# Esquema.net
KiCad netlist of a schematic drawn in Altium Designer
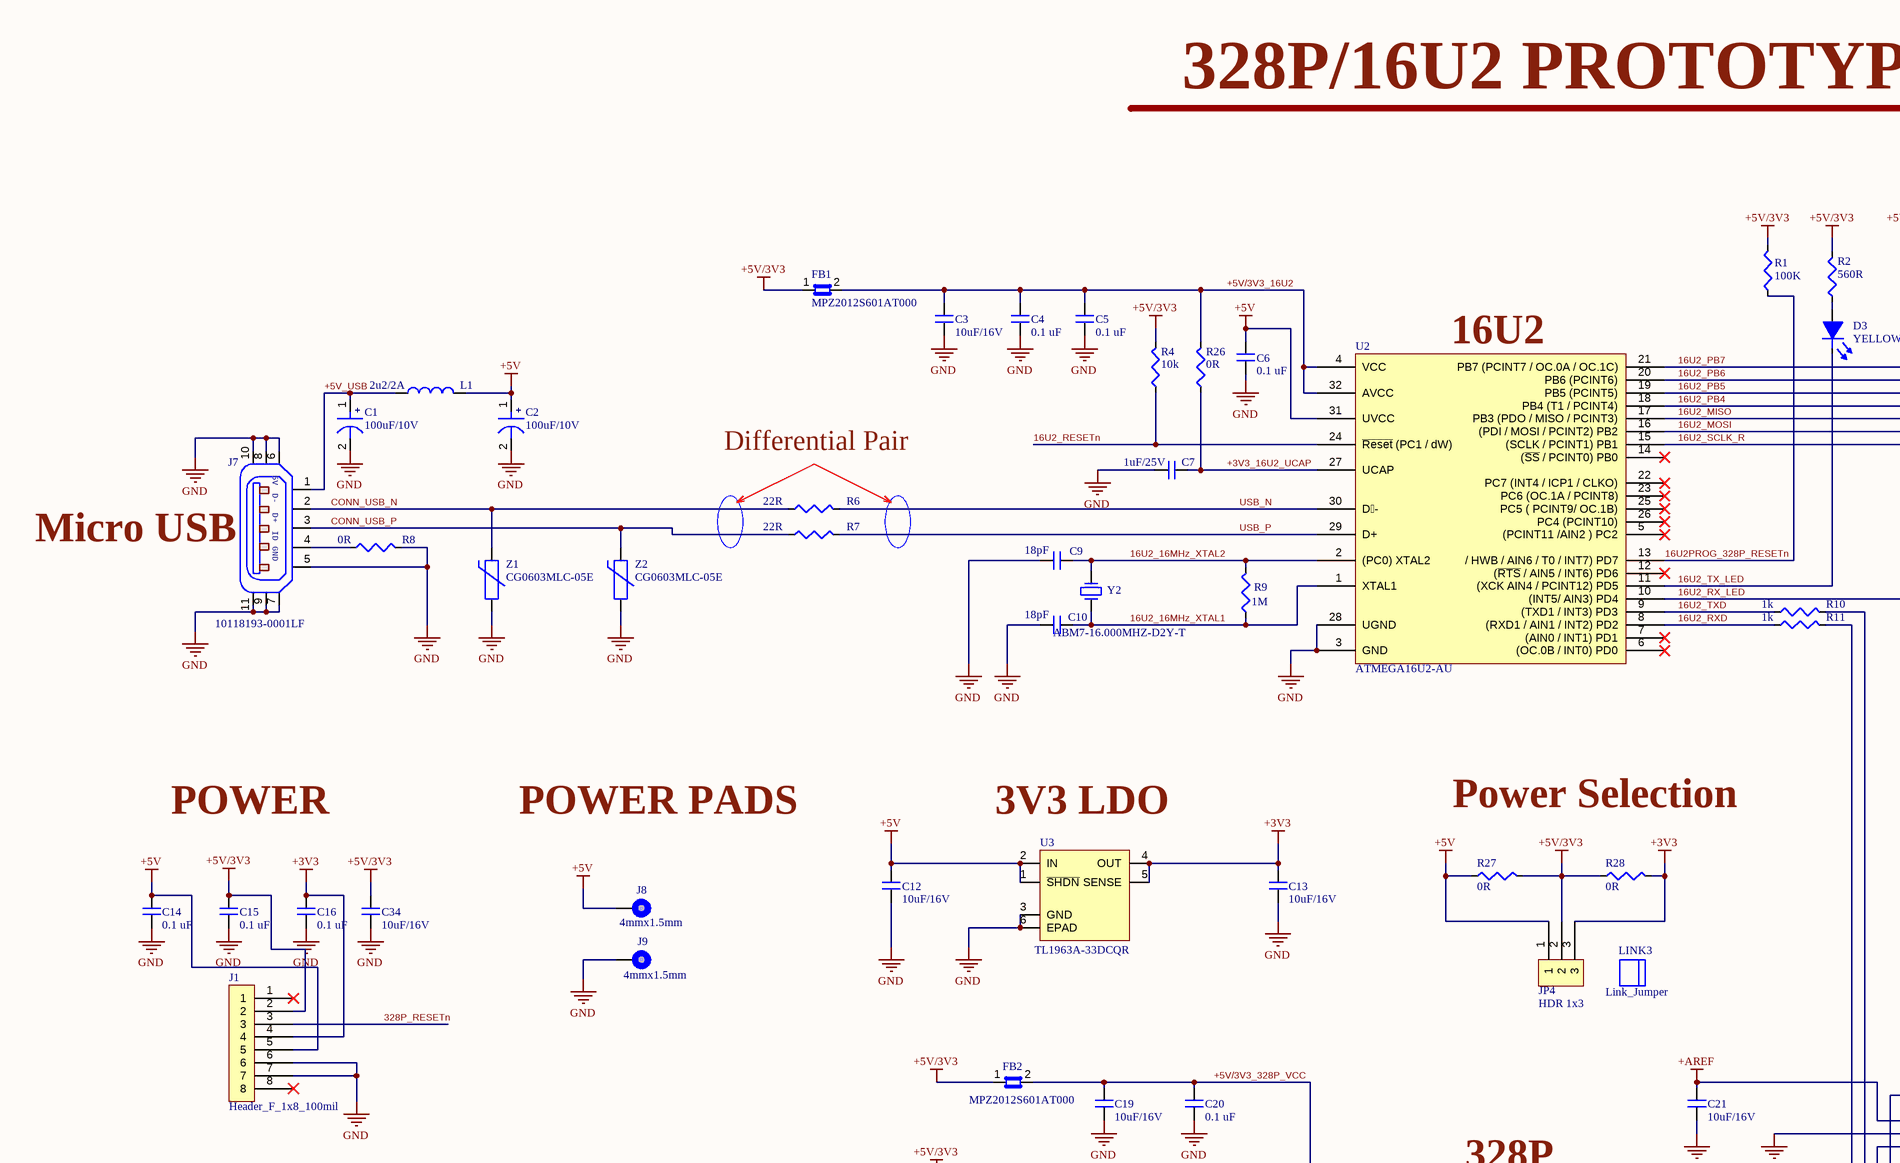
[diagram p0: Esquema.SchDoc, top left]
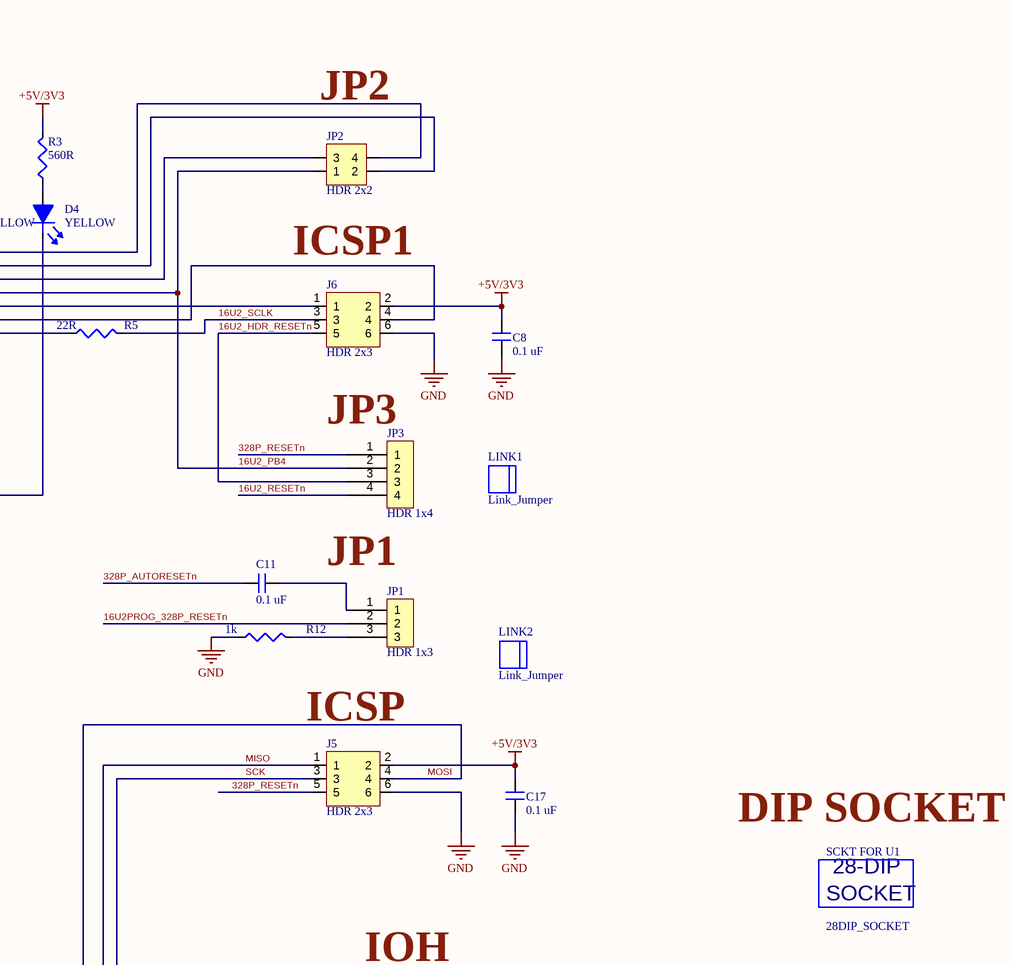
[diagram p1: Esquema.SchDoc, top right]
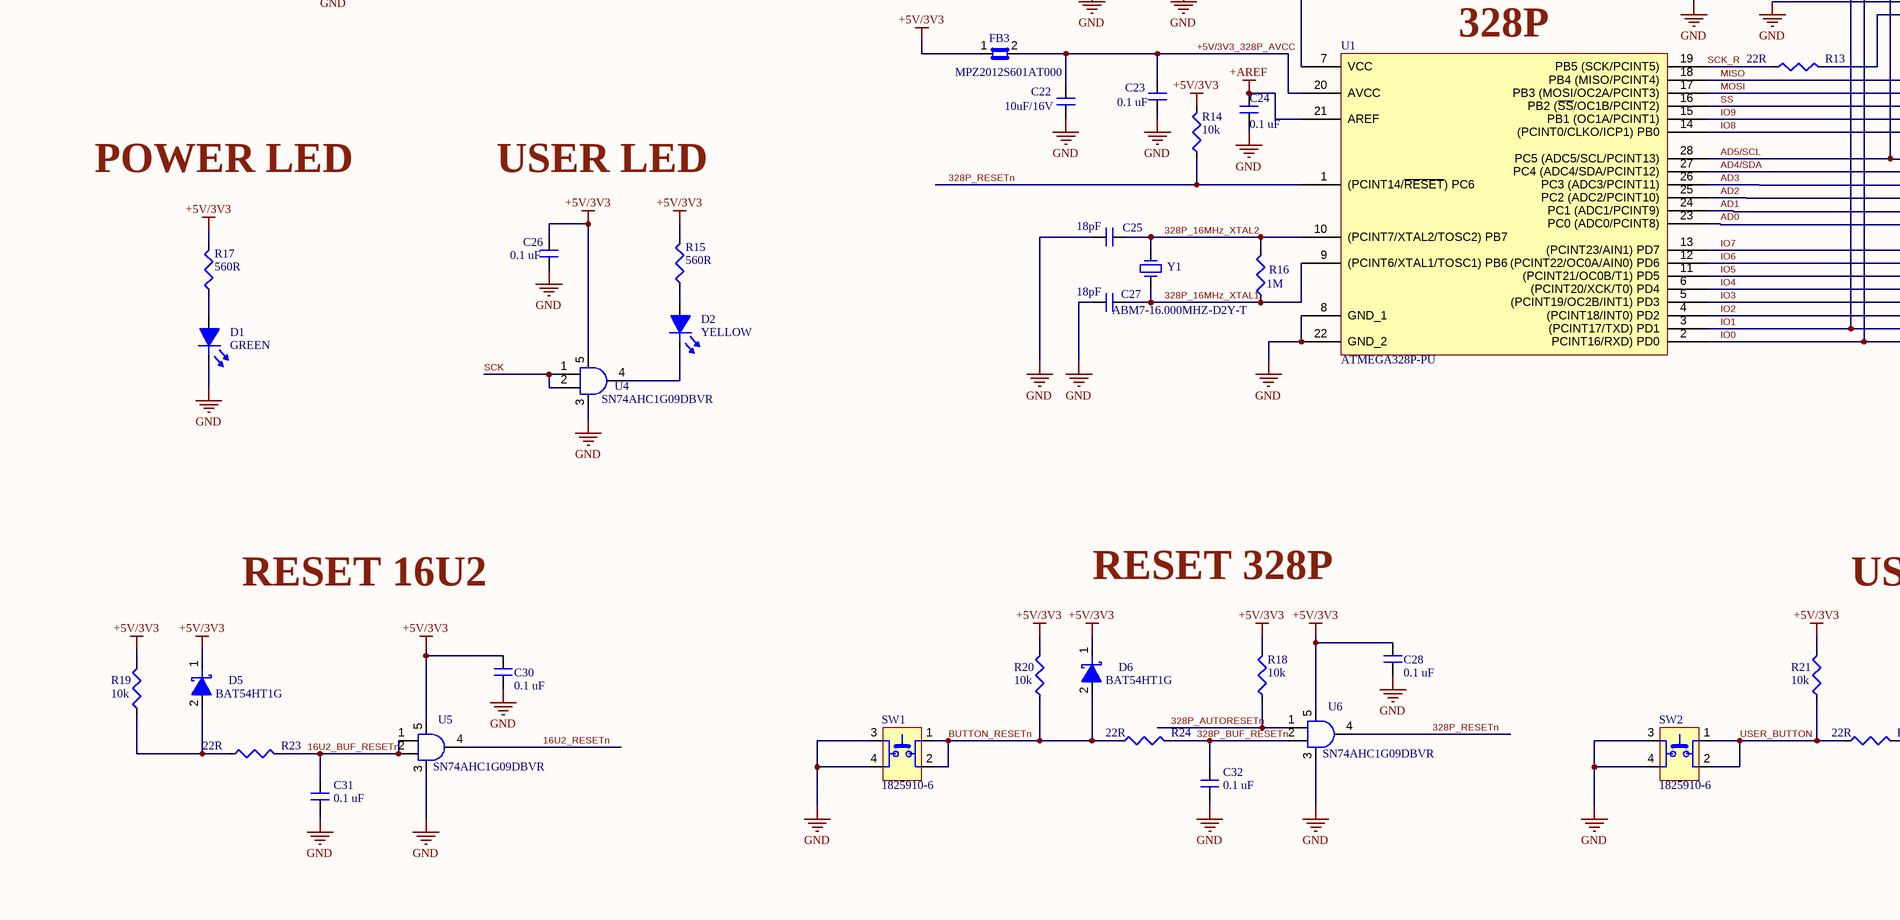
[diagram p2: Esquema.SchDoc, bottom left]
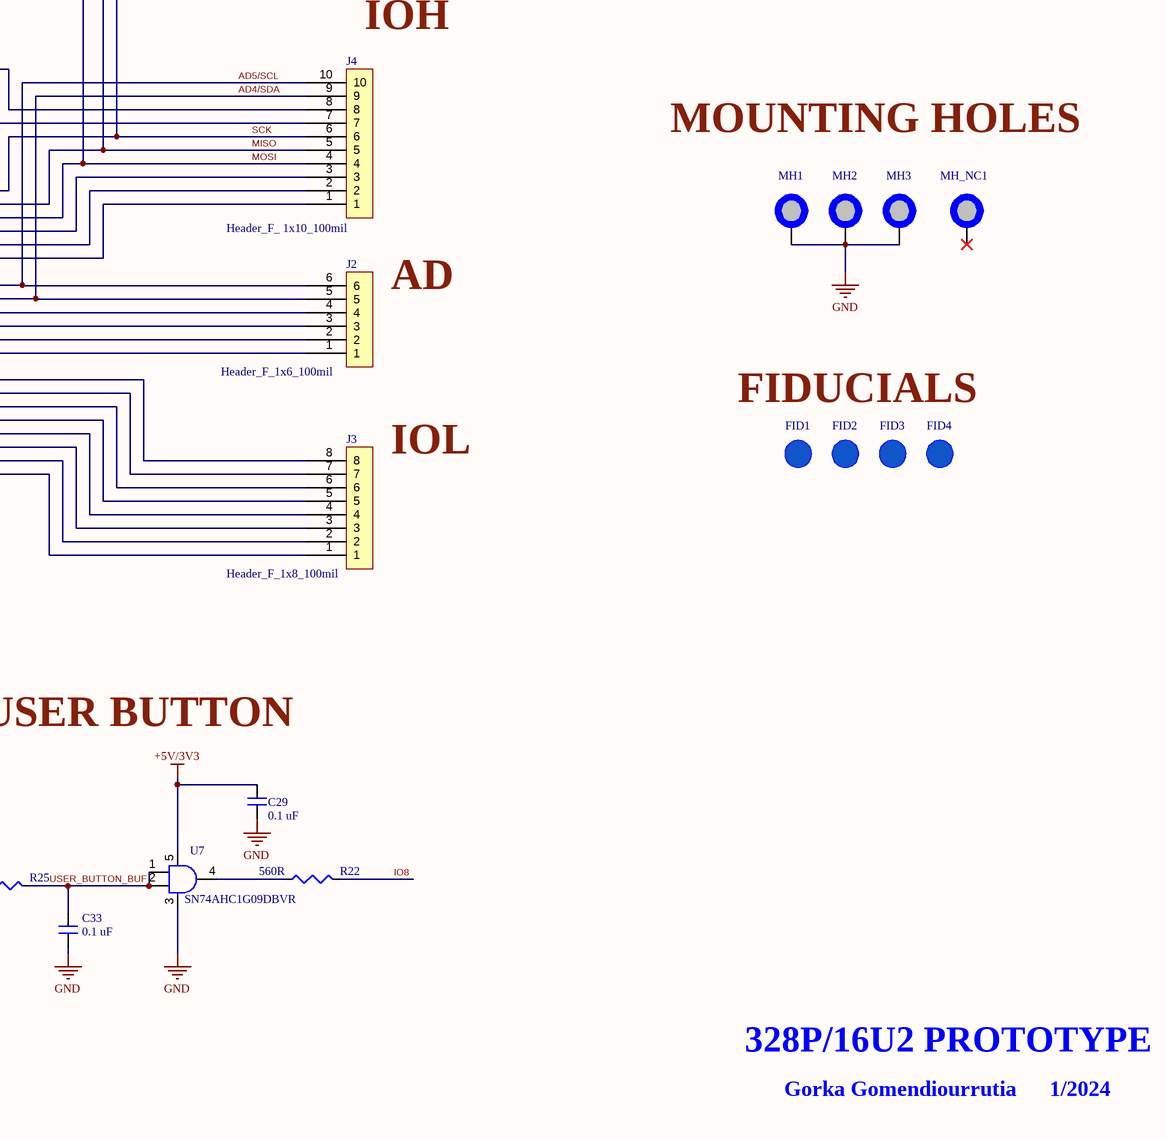
[diagram p3: Esquema.SchDoc, bottom right]

(export (version "E")
  (design (tool "Eeschema 10.0.6"))
  (components
    (comp (ref "C1")
      (value "100uF/10V")
      (footprint "CAP_ALU_C_SIZE")
      (description "Aluminum Electrolytic Capacitor, 100 uF, 10 V, ± 20%, 1000 hours @ 85°C, Radial Can - SMD")
      (fields
        (field (name "MANUFACTURER") "Panasonic")
        (field (name "MANUFACTURER PART NUMBER") "EEE-1AA101WR")
      )
      (libsource (lib "Librerias esquema") (part "EEE-1AA101WR"))
    )
    (comp (ref "C2")
      (value "100uF/10V")
      (footprint "CAP_ALU_C_SIZE")
      (description "Aluminum Electrolytic Capacitor, 100 uF, 10 V, ± 20%, 1000 hours @ 85°C, Radial Can - SMD")
      (fields
        (field (name "MANUFACTURER") "Panasonic")
        (field (name "MANUFACTURER PART NUMBER") "EEE-1AA101WR")
      )
      (libsource (lib "Librerias esquema") (part "EEE-1AA101WR"))
    )
    (comp (ref "C3")
      (value "10uF/16V")
      (footprint "0805")
      (description "C Series 0805 10 uF 16 V ±10 % Tolerance X5R SMT Multilayer Ceramic Capacitor")
      (fields
        (field (name "MANUFACTURER") "TDK")
        (field (name "MANUFACTURER PART NUMBER") "C2012X5R1C106K085AC")
      )
      (libsource (lib "Librerias esquema") (part "C2012X5R1C106K085AC"))
    )
    (comp (ref "C4")
      (value "0.1 uF")
      (footprint "0805")
      (description "Multilayer Ceramic Capacitor, 0.1 uF, 50 V, ± 10%, X7R, 0805 [2012 Metric]")
      (fields
        (field (name "MANUFACTURER") "TDK")
        (field (name "MANUFACTURER PART NUMBER") "C2012X7R1H104K085AA")
      )
      (libsource (lib "Librerias esquema") (part "C2012X7R1H104K085AA"))
    )
    (comp (ref "C5")
      (value "0.1 uF")
      (footprint "0805")
      (description "Multilayer Ceramic Capacitor, 0.1 uF, 50 V, ± 10%, X7R, 0805 [2012 Metric]")
      (fields
        (field (name "MANUFACTURER") "TDK")
        (field (name "MANUFACTURER PART NUMBER") "C2012X7R1H104K085AA")
      )
      (libsource (lib "Librerias esquema") (part "C2012X7R1H104K085AA"))
    )
    (comp (ref "C6")
      (value "0.1 uF")
      (footprint "0805")
      (description "Multilayer Ceramic Capacitor, 0.1 uF, 50 V, ± 10%, X7R, 0805 [2012 Metric]")
      (fields
        (field (name "MANUFACTURER") "TDK")
        (field (name "MANUFACTURER PART NUMBER") "C2012X7R1H104K085AA")
      )
      (libsource (lib "Librerias esquema") (part "C2012X7R1H104K085AA"))
    )
    (comp (ref "C7")
      (value "1uF/25V")
      (footprint "0805")
      (description "C Series 0805 1 uF 25 V ±10 % Tolerance X5R SMT Multilayer Ceramic Capacitor")
      (fields
        (field (name "MANUFACTURER") "TDK")
        (field (name "MANUFACTURER PART NUMBER") "C2012X5R1E105K085AC")
      )
      (libsource (lib "Librerias esquema") (part "C2012X5R1E105K085AC"))
    )
    (comp (ref "C8")
      (value "0.1 uF")
      (footprint "0805")
      (description "Multilayer Ceramic Capacitor, 0.1 uF, 50 V, ± 10%, X7R, 0805 [2012 Metric]")
      (fields
        (field (name "MANUFACTURER") "TDK")
        (field (name "MANUFACTURER PART NUMBER") "C2012X7R1H104K085AA")
      )
      (libsource (lib "Librerias esquema") (part "C2012X7R1H104K085AA"))
    )
    (comp (ref "C9")
      (value "18pF")
      (footprint "0805")
      (description "Multilayer Ceramic Capacitor, 18 pF, 50 V, ± 5%, C0G (NP0), 0805 [2012 Metric]")
      (fields
        (field (name "MANUFACTURER") "KEMET")
        (field (name "MANUFACTURER PART NUMBER") "C0805C180J5GACTU")
      )
      (libsource (lib "Librerias esquema") (part "C0805C180J5GACTU"))
    )
    (comp (ref "C10")
      (value "18pF")
      (footprint "0805")
      (description "Multilayer Ceramic Capacitor, 18 pF, 50 V, ± 5%, C0G (NP0), 0805 [2012 Metric]")
      (fields
        (field (name "MANUFACTURER") "KEMET")
        (field (name "MANUFACTURER PART NUMBER") "C0805C180J5GACTU")
      )
      (libsource (lib "Librerias esquema") (part "C0805C180J5GACTU"))
    )
    (comp (ref "C11")
      (value "0.1 uF")
      (footprint "0805")
      (description "Multilayer Ceramic Capacitor, 0.1 uF, 50 V, ± 10%, X7R, 0805 [2012 Metric]")
      (fields
        (field (name "MANUFACTURER") "TDK")
        (field (name "MANUFACTURER PART NUMBER") "C2012X7R1H104K085AA")
      )
      (libsource (lib "Librerias esquema") (part "C2012X7R1H104K085AA"))
    )
    (comp (ref "C12")
      (value "10uF/16V")
      (footprint "0805")
      (description "C Series 0805 10 uF 16 V ±10 % Tolerance X5R SMT Multilayer Ceramic Capacitor")
      (fields
        (field (name "MANUFACTURER") "TDK")
        (field (name "MANUFACTURER PART NUMBER") "C2012X5R1C106K085AC")
      )
      (libsource (lib "Librerias esquema") (part "C2012X5R1C106K085AC"))
    )
    (comp (ref "C13")
      (value "10uF/16V")
      (footprint "0805")
      (description "C Series 0805 10 uF 16 V ±10 % Tolerance X5R SMT Multilayer Ceramic Capacitor")
      (fields
        (field (name "MANUFACTURER") "TDK")
        (field (name "MANUFACTURER PART NUMBER") "C2012X5R1C106K085AC")
      )
      (libsource (lib "Librerias esquema") (part "C2012X5R1C106K085AC"))
    )
    (comp (ref "C14")
      (value "0.1 uF")
      (footprint "0805")
      (description "Multilayer Ceramic Capacitor, 0.1 uF, 50 V, ± 10%, X7R, 0805 [2012 Metric]")
      (fields
        (field (name "MANUFACTURER") "TDK")
        (field (name "MANUFACTURER PART NUMBER") "C2012X7R1H104K085AA")
      )
      (libsource (lib "Librerias esquema") (part "C2012X7R1H104K085AA"))
    )
    (comp (ref "C15")
      (value "0.1 uF")
      (footprint "0805")
      (description "Multilayer Ceramic Capacitor, 0.1 uF, 50 V, ± 10%, X7R, 0805 [2012 Metric]")
      (fields
        (field (name "MANUFACTURER") "TDK")
        (field (name "MANUFACTURER PART NUMBER") "C2012X7R1H104K085AA")
      )
      (libsource (lib "Librerias esquema") (part "C2012X7R1H104K085AA"))
    )
    (comp (ref "C16")
      (value "0.1 uF")
      (footprint "0805")
      (description "Multilayer Ceramic Capacitor, 0.1 uF, 50 V, ± 10%, X7R, 0805 [2012 Metric]")
      (fields
        (field (name "MANUFACTURER") "TDK")
        (field (name "MANUFACTURER PART NUMBER") "C2012X7R1H104K085AA")
      )
      (libsource (lib "Librerias esquema") (part "C2012X7R1H104K085AA"))
    )
    (comp (ref "C17")
      (value "0.1 uF")
      (footprint "0805")
      (description "Multilayer Ceramic Capacitor, 0.1 uF, 50 V, ± 10%, X7R, 0805 [2012 Metric]")
      (fields
        (field (name "MANUFACTURER") "TDK")
        (field (name "MANUFACTURER PART NUMBER") "C2012X7R1H104K085AA")
      )
      (libsource (lib "Librerias esquema") (part "C2012X7R1H104K085AA"))
    )
    (comp (ref "C19")
      (value "10uF/16V")
      (footprint "0805")
      (description "C Series 0805 10 uF 16 V ±10 % Tolerance X5R SMT Multilayer Ceramic Capacitor")
      (fields
        (field (name "MANUFACTURER") "TDK")
        (field (name "MANUFACTURER PART NUMBER") "C2012X5R1C106K085AC")
      )
      (libsource (lib "Librerias esquema") (part "C2012X5R1C106K085AC"))
    )
    (comp (ref "C20")
      (value "0.1 uF")
      (footprint "0805")
      (description "Multilayer Ceramic Capacitor, 0.1 uF, 50 V, ± 10%, X7R, 0805 [2012 Metric]")
      (fields
        (field (name "MANUFACTURER") "TDK")
        (field (name "MANUFACTURER PART NUMBER") "C2012X7R1H104K085AA")
      )
      (libsource (lib "Librerias esquema") (part "C2012X7R1H104K085AA"))
    )
    (comp (ref "C21")
      (value "10uF/16V")
      (footprint "0805")
      (description "C Series 0805 10 uF 16 V ±10 % Tolerance X5R SMT Multilayer Ceramic Capacitor")
      (fields
        (field (name "MANUFACTURER") "TDK")
        (field (name "MANUFACTURER PART NUMBER") "C2012X5R1C106K085AC")
      )
      (libsource (lib "Librerias esquema") (part "C2012X5R1C106K085AC"))
    )
    (comp (ref "C22")
      (value "10uF/16V")
      (footprint "0805")
      (description "C Series 0805 10 uF 16 V ±10 % Tolerance X5R SMT Multilayer Ceramic Capacitor")
      (fields
        (field (name "MANUFACTURER") "TDK")
        (field (name "MANUFACTURER PART NUMBER") "C2012X5R1C106K085AC")
      )
      (libsource (lib "Librerias esquema") (part "C2012X5R1C106K085AC"))
    )
    (comp (ref "C23")
      (value "0.1 uF")
      (footprint "0805")
      (description "Multilayer Ceramic Capacitor, 0.1 uF, 50 V, ± 10%, X7R, 0805 [2012 Metric]")
      (fields
        (field (name "MANUFACTURER") "TDK")
        (field (name "MANUFACTURER PART NUMBER") "C2012X7R1H104K085AA")
      )
      (libsource (lib "Librerias esquema") (part "C2012X7R1H104K085AA"))
    )
    (comp (ref "C24")
      (value "0.1 uF")
      (footprint "0805")
      (description "Multilayer Ceramic Capacitor, 0.1 uF, 50 V, ± 10%, X7R, 0805 [2012 Metric]")
      (fields
        (field (name "MANUFACTURER") "TDK")
        (field (name "MANUFACTURER PART NUMBER") "C2012X7R1H104K085AA")
      )
      (libsource (lib "Librerias esquema") (part "C2012X7R1H104K085AA"))
    )
    (comp (ref "C25")
      (value "18pF")
      (footprint "0805")
      (description "Multilayer Ceramic Capacitor, 18 pF, 50 V, ± 5%, C0G (NP0), 0805 [2012 Metric]")
      (fields
        (field (name "MANUFACTURER") "KEMET")
        (field (name "MANUFACTURER PART NUMBER") "C0805C180J5GACTU")
      )
      (libsource (lib "Librerias esquema") (part "C0805C180J5GACTU"))
    )
    (comp (ref "C26")
      (value "0.1 uF")
      (footprint "0805")
      (description "Multilayer Ceramic Capacitor, 0.1 uF, 50 V, ± 10%, X7R, 0805 [2012 Metric]")
      (fields
        (field (name "MANUFACTURER") "TDK")
        (field (name "MANUFACTURER PART NUMBER") "C2012X7R1H104K085AA")
      )
      (libsource (lib "Librerias esquema") (part "C2012X7R1H104K085AA"))
    )
    (comp (ref "C27")
      (value "18pF")
      (footprint "0805")
      (description "Multilayer Ceramic Capacitor, 18 pF, 50 V, ± 5%, C0G (NP0), 0805 [2012 Metric]")
      (fields
        (field (name "MANUFACTURER") "KEMET")
        (field (name "MANUFACTURER PART NUMBER") "C0805C180J5GACTU")
      )
      (libsource (lib "Librerias esquema") (part "C0805C180J5GACTU"))
    )
    (comp (ref "C28")
      (value "0.1 uF")
      (footprint "0805")
      (description "Multilayer Ceramic Capacitor, 0.1 uF, 50 V, ± 10%, X7R, 0805 [2012 Metric]")
      (fields
        (field (name "MANUFACTURER") "TDK")
        (field (name "MANUFACTURER PART NUMBER") "C2012X7R1H104K085AA")
      )
      (libsource (lib "Librerias esquema") (part "C2012X7R1H104K085AA"))
    )
    (comp (ref "C29")
      (value "0.1 uF")
      (footprint "0805")
      (description "Multilayer Ceramic Capacitor, 0.1 uF, 50 V, ± 10%, X7R, 0805 [2012 Metric]")
      (fields
        (field (name "MANUFACTURER") "TDK")
        (field (name "MANUFACTURER PART NUMBER") "C2012X7R1H104K085AA")
      )
      (libsource (lib "Librerias esquema") (part "C2012X7R1H104K085AA"))
    )
    (comp (ref "C30")
      (value "0.1 uF")
      (footprint "0805")
      (description "Multilayer Ceramic Capacitor, 0.1 uF, 50 V, ± 10%, X7R, 0805 [2012 Metric]")
      (fields
        (field (name "MANUFACTURER") "TDK")
        (field (name "MANUFACTURER PART NUMBER") "C2012X7R1H104K085AA")
      )
      (libsource (lib "Librerias esquema") (part "C2012X7R1H104K085AA"))
    )
    (comp (ref "C31")
      (value "0.1 uF")
      (footprint "0805")
      (description "Multilayer Ceramic Capacitor, 0.1 uF, 50 V, ± 10%, X7R, 0805 [2012 Metric]")
      (fields
        (field (name "MANUFACTURER") "TDK")
        (field (name "MANUFACTURER PART NUMBER") "C2012X7R1H104K085AA")
      )
      (libsource (lib "Librerias esquema") (part "C2012X7R1H104K085AA"))
    )
    (comp (ref "C32")
      (value "0.1 uF")
      (footprint "0805")
      (description "Multilayer Ceramic Capacitor, 0.1 uF, 50 V, ± 10%, X7R, 0805 [2012 Metric]")
      (fields
        (field (name "MANUFACTURER") "TDK")
        (field (name "MANUFACTURER PART NUMBER") "C2012X7R1H104K085AA")
      )
      (libsource (lib "Librerias esquema") (part "C2012X7R1H104K085AA"))
    )
    (comp (ref "C33")
      (value "0.1 uF")
      (footprint "0805")
      (description "Multilayer Ceramic Capacitor, 0.1 uF, 50 V, ± 10%, X7R, 0805 [2012 Metric]")
      (fields
        (field (name "MANUFACTURER") "TDK")
        (field (name "MANUFACTURER PART NUMBER") "C2012X7R1H104K085AA")
      )
      (libsource (lib "Librerias esquema") (part "C2012X7R1H104K085AA"))
    )
    (comp (ref "C34")
      (value "10uF/16V")
      (footprint "0805")
      (description "C Series 0805 10 uF 16 V ±10 % Tolerance X5R SMT Multilayer Ceramic Capacitor")
      (fields
        (field (name "MANUFACTURER") "TDK")
        (field (name "MANUFACTURER PART NUMBER") "C2012X5R1C106K085AC")
      )
      (libsource (lib "Librerias esquema") (part "C2012X5R1C106K085AC"))
    )
    (comp (ref "D1")
      (value "GREEN")
      (footprint "LED 0603")
      (description "LED Low-Power Uni-Color Green 520nm 3.4V 2-Pin Chip LED T/R")
      (fields
        (field (name "MANUFACTURER") "Broadcom Avago")
        (field (name "MANUFACTURER PART NUMBER") "HSMQ-C191")
      )
      (libsource (lib "Librerias esquema") (part "HSMQ-C191"))
    )
    (comp (ref "D2")
      (value "YELLOW")
      (footprint "LED 0603")
      (description "LED Uni-Color Yellow 591nm Automotive 2-Pin Chip 0603(1608Metric) T/R")
      (fields
        (field (name "MANUFACTURER") "Osram Opto")
        (field (name "MANUFACTURER PART NUMBER") "LYL29K-H1K2-26-Z")
      )
      (libsource (lib "Librerias esquema") (part "LYL29K-H1K2-26-Z"))
    )
    (comp (ref "D3")
      (value "YELLOW")
      (footprint "LED 0603")
      (description "LED Uni-Color Yellow 591nm Automotive 2-Pin Chip 0603(1608Metric) T/R")
      (fields
        (field (name "MANUFACTURER") "Osram Opto")
        (field (name "MANUFACTURER PART NUMBER") "LYL29K-H1K2-26-Z")
      )
      (libsource (lib "Librerias esquema") (part "LYL29K-H1K2-26-Z"))
    )
    (comp (ref "D4")
      (value "YELLOW")
      (footprint "LED 0603")
      (description "LED Uni-Color Yellow 591nm Automotive 2-Pin Chip 0603(1608Metric) T/R")
      (fields
        (field (name "MANUFACTURER") "Osram Opto")
        (field (name "MANUFACTURER PART NUMBER") "LYL29K-H1K2-26-Z")
      )
      (libsource (lib "Librerias esquema") (part "LYL29K-H1K2-26-Z"))
    )
    (comp (ref "D5")
      (value "BAT54HT1G")
      (footprint "SOD323")
      (description "Small Signal Schottky Diode, Single, 30 V, 200 Ma, 800 Mv, 600 Ma, 150 C")
      (fields (field (name "MANUFACTURER") "ON Semiconductor / Fairchild"))
      (libsource (lib "Librerias esquema") (part "BAT54HT1G"))
    )
    (comp (ref "D6")
      (value "BAT54HT1G")
      (footprint "SOD323")
      (description "Small Signal Schottky Diode, Single, 30 V, 200 Ma, 800 Mv, 600 Ma, 150 C")
      (fields (field (name "MANUFACTURER") "ON Semiconductor / Fairchild"))
      (libsource (lib "Librerias esquema") (part "BAT54HT1G"))
    )
    (comp (ref "FB1")
      (value "MPZ2012S601AT000")
      (footprint "0805")
      (description "Ferrite Beads Multi-Layer Power 600Ohm 25% 100MHz 2A 100mOhm DCR 0805 T/R")
      (fields (field (name "MANUFACTURER") "TDK") (field (name "TOLERANCE") "25%"))
      (libsource (lib "Librerias esquema") (part "MPZ2012S601AT000"))
    )
    (comp (ref "FB2")
      (value "MPZ2012S601AT000")
      (footprint "0805")
      (description "Ferrite Beads Multi-Layer Power 600Ohm 25% 100MHz 2A 100mOhm DCR 0805 T/R")
      (fields (field (name "MANUFACTURER") "TDK") (field (name "TOLERANCE") "25%"))
      (libsource (lib "Librerias esquema") (part "MPZ2012S601AT000"))
    )
    (comp (ref "FB3")
      (value "MPZ2012S601AT000")
      (footprint "0805")
      (description "Ferrite Beads Multi-Layer Power 600Ohm 25% 100MHz 2A 100mOhm DCR 0805 T/R")
      (fields (field (name "MANUFACTURER") "TDK") (field (name "TOLERANCE") "25%"))
      (libsource (lib "Librerias esquema") (part "MPZ2012S601AT000"))
    )
    (comp (ref "FID1")
      (value "40x120mil")
      (footprint "FIDUCIAL_40x120mil")
      (description "Fiducial 40milx120mil mask")
      (libsource (lib "Librerias esquema") (part "FIDUCIAL_1mm"))
    )
    (comp (ref "FID2")
      (value "40x120mil")
      (footprint "FIDUCIAL_40x120mil")
      (description "Fiducial 40milx120mil mask")
      (libsource (lib "Librerias esquema") (part "FIDUCIAL_1mm"))
    )
    (comp (ref "FID3")
      (value "40x120mil")
      (footprint "FIDUCIAL_40x120mil")
      (description "Fiducial 40milx120mil mask")
      (libsource (lib "Librerias esquema") (part "FIDUCIAL_1mm"))
    )
    (comp (ref "FID4")
      (value "40x120mil")
      (footprint "FIDUCIAL_40x120mil")
      (description "Fiducial 40milx120mil mask")
      (libsource (lib "Librerias esquema") (part "FIDUCIAL_1mm"))
    )
    (comp (ref "J1")
      (value "Header_F_1x8_100mil")
      (footprint "Header_F_1x8_100mil")
      (description "2.54mm (0.1\") Pitch SIL Vertical PC Tail Socket Assembly, selective gold + tin, 8 contacts")
      (fields (field (name "MANUFACTURER") "Harwin") (field (name "MANUFACTURER PART NUMBER") "M20-7820842"))
      (libsource (lib "Librerias esquema") (part "M20-7820842"))
    )
    (comp (ref "J2")
      (value "Header_F_1x6_100mil")
      (footprint "Header_F_1x6_100mil")
      (description "2.54mm (0.1\") Pitch SIL Vertical PC Tail Socket Assembly, selective gold + tin, 6 contacts")
      (fields (field (name "MANUFACTURER") "Harwin") (field (name "MANUFACTURER PART NUMBER") "M20-7820642"))
      (libsource (lib "Librerias esquema") (part "M20-7820642"))
    )
    (comp (ref "J3")
      (value "Header_F_1x8_100mil")
      (footprint "Header_F_1x8_100mil")
      (description "2.54mm (0.1\") Pitch SIL Vertical PC Tail Socket Assembly, selective gold + tin, 8 contacts")
      (fields (field (name "MANUFACTURER") "Harwin") (field (name "MANUFACTURER PART NUMBER") "M20-7820842"))
      (libsource (lib "") (part "M20-7820842_1"))
    )
    (comp (ref "J4")
      (value "Header_F_ 1x10_100mil")
      (footprint "Header_F_1x10_100mil")
      (description "2.54mm (0.1\") Pitch SIL Vertical PC Tail Socket Assembly, tin, 10 contacts")
      (fields (field (name "MANUFACTURER") "Harwin") (field (name "MANUFACTURER PART NUMBER") "M20-7821046"))
      (libsource (lib "Librerias esquema") (part "M20-7821046"))
    )
    (comp (ref "J5")
      (value "HDR 2x3")
      (footprint "HDR 2x3 100mil")
      (description "Conn Unshrouded Header HDR 6 POS 2.54mm Solder ST Top Entry Thru-Hole BergStik® Bulk")
      (fields
        (field (name "MANUFACTURER") "Amphenol ICC / FCI")
        (field (name "MANUFACTURER PART NUMBER") "67997-106HLF")
      )
      (libsource (lib "Librerias esquema") (part "67997-106HLF"))
    )
    (comp (ref "J6")
      (value "HDR 2x3")
      (footprint "HDR 2x3 100mil")
      (description "Conn Unshrouded Header HDR 6 POS 2.54mm Solder ST Top Entry Thru-Hole BergStik® Bulk")
      (fields
        (field (name "MANUFACTURER") "Amphenol ICC / FCI")
        (field (name "MANUFACTURER PART NUMBER") "67997-106HLF")
      )
      (libsource (lib "Librerias esquema") (part "67997-106HLF"))
    )
    (comp (ref "J7")
      (value "10118193-0001LF")
      (footprint "MicroUSB_10118193-0001LF")
      (description "FCI Right Angle Surface Mount Mount Female USB Connector; 100 V ac; 1.8A")
      (fields (field (name "MANUFACTURER") "Amphenol ICC / FCI"))
      (libsource (lib "Librerias esquema") (part "10118193-0001LF"))
    )
    (comp (ref "J8")
      (value "4mmx1.5mm")
      (footprint "PAD_4mmx1.5mm")
      (description "Hole Pad 3mmx1.5mm")
      (libsource (lib "Librerias esquema") (part "PAD_HOLE_4mmx1.5mm"))
    )
    (comp (ref "J9")
      (value "4mmx1.5mm")
      (footprint "PAD_4mmx1.5mm")
      (description "Hole Pad 3mmx1.5mm")
      (libsource (lib "Librerias esquema") (part "PAD_HOLE_4mmx1.5mm"))
    )
    (comp (ref "JP1")
      (value "HDR 1x3")
      (footprint "HDR_1x3")
      (description "Conn Unshrouded Header HDR 3 POS 2.54mm Solder ST Top Entry Thru-Hole BergStik® Bulk")
      (fields
        (field (name "MANUFACTURER") "Amphenol ICC / FCI")
        (field (name "MANUFACTURER PART NUMBER") "68001-203HLF")
      )
      (libsource (lib "Librerias esquema") (part "68001-203HLF"))
    )
    (comp (ref "JP2")
      (value "HDR 2x2")
      (footprint "HDR 2x2 100mil")
      (description "Conn Unshrouded Header HDR 4 POS 2.54mm Solder ST Top Entry Thru-Hole BergStik® Bulk")
      (fields
        (field (name "MANUFACTURER") "AMPHENOL ICC (FCI)")
        (field (name "MANUFACTURER PART NUMBER") "68602-204HLF")
      )
      (libsource (lib "Librerias esquema") (part "68602-204HLF"))
    )
    (comp (ref "JP3")
      (value "HDR 1x4")
      (footprint "HDR_1x4_2.54mm")
      (description "Conn Unshrouded Header HDR 4 POS 2.54mm Solder ST Top Entry Thru-Hole BergStik® Bulk")
      (fields
        (field (name "MANUFACTURER") "Amphenol ICC / FCI")
        (field (name "MANUFACTURER PART NUMBER") "68002-404HLF")
      )
      (libsource (lib "Librerias esquema") (part "68002-404HLF"))
    )
    (comp (ref "JP4")
      (value "HDR 1x3")
      (footprint "HDR_1x3")
      (description "Conn Unshrouded Header HDR 3 POS 2.54mm Solder ST Top Entry Thru-Hole BergStik® Bulk")
      (fields
        (field (name "MANUFACTURER") "Amphenol ICC / FCI")
        (field (name "MANUFACTURER PART NUMBER") "68001-203HLF")
      )
      (libsource (lib "") (part "68001-203HLF_1"))
    )
    (comp (ref "L1")
      (value "2u2/2A")
      (footprint "1210_2u2_Inductor")
      (description "Inductor Chip Molded Wirewound 2.2uH 20% 1008 T/R")
      (fields
        (field (name "MANUFACTURER") "KEMET")
        (field (name "MANUFACTURER PART NUMBER") "L1008C2R2MDMIT")
      )
      (libsource (lib "Librerias esquema") (part "L1008C2R2MDMIT"))
    )
    (comp (ref "LINK1")
      (value "Link_Jumper")
      (description "2 Position 2.54 mm Centerline Single Circuit Open Top Jumper")
      (fields
        (field (name "MANUFACTURER") "Sullins")
        (field (name "MANUFACTURER PART NUMBER") "QPC02SXGN-RC")
      )
      (libsource (lib "Librerias esquema") (part "QPC02SXGN-RC"))
    )
    (comp (ref "LINK2")
      (value "Link_Jumper")
      (description "2 Position 2.54 mm Centerline Single Circuit Open Top Jumper")
      (fields
        (field (name "MANUFACTURER") "Sullins")
        (field (name "MANUFACTURER PART NUMBER") "QPC02SXGN-RC")
      )
      (libsource (lib "Librerias esquema") (part "QPC02SXGN-RC"))
    )
    (comp (ref "LINK3")
      (value "Link_Jumper")
      (description "2 Position 2.54 mm Centerline Single Circuit Open Top Jumper")
      (fields
        (field (name "MANUFACTURER") "Sullins")
        (field (name "MANUFACTURER PART NUMBER") "QPC02SXGN-RC")
      )
      (libsource (lib "Librerias esquema") (part "QPC02SXGN-RC"))
    )
    (comp (ref "MH1")
      (value "MH_7.4x3.2mm")
      (footprint "MH")
      (libsource (lib "Librerias esquema") (part "MH_7.4mmx3.2mm"))
    )
    (comp (ref "MH2")
      (value "MH_7.4x3.2mm")
      (footprint "MH")
      (libsource (lib "Librerias esquema") (part "MH_7.4mmx3.2mm"))
    )
    (comp (ref "MH3")
      (value "MH_7.4x3.2mm")
      (footprint "MH")
      (libsource (lib "Librerias esquema") (part "MH_7.4mmx3.2mm"))
    )
    (comp (ref "MH_NC1")
      (value "MHNC_7.4mmx3.2mm")
      (footprint "MH_NonPlated_7.4mmx3.2mmHole")
      (libsource (lib "Librerias esquema") (part "MH_NC_7.4mmx3.2mm"))
    )
    (comp (ref "R1")
      (value "100K")
      (footprint "R0805")
      (description "SMD Chip Resistor, 100 kOhm, ± 1%, 125 mW, 0805 [2012 Metric], Thick Film, General Purpose")
      (fields
        (field (name "MANUFACTURER") "Yageo")
        (field (name "MANUFACTURER PART NUMBER") "RC0805FR-07100KL")
      )
      (libsource (lib "Librerias esquema") (part "RC0805FR-07100KL"))
    )
    (comp (ref "R2")
      (value "560R")
      (footprint "R0805")
      (description "Res General Purpose Thick Film 0805 560 Ohm 1% 1/8W ±100ppm/°C Molded Paper T/R")
      (fields
        (field (name "MANUFACTURER") "Yageo")
        (field (name "MANUFACTURER PART NUMBER") "RC0805FR-07560RL")
      )
      (libsource (lib "Librerias esquema") (part "RC0805FR-07560RL"))
    )
    (comp (ref "R3")
      (value "560R")
      (footprint "R0805")
      (description "Res General Purpose Thick Film 0805 560 Ohm 1% 1/8W ±100ppm/°C Molded Paper T/R")
      (fields
        (field (name "MANUFACTURER") "Yageo")
        (field (name "MANUFACTURER PART NUMBER") "RC0805FR-07560RL")
      )
      (libsource (lib "Librerias esquema") (part "RC0805FR-07560RL"))
    )
    (comp (ref "R4")
      (value "10k")
      (footprint "0805")
      (description "SMD Chip Resistor, 10 kOhm, ± 1%, 125 mW, 0805 [2012 Metric], Thick Film, General Purpose")
      (fields
        (field (name "MANUFACTURER") "Yageo")
        (field (name "MANUFACTURER PART NUMBER") "RC0805FR-0710KL")
      )
      (libsource (lib "Librerias esquema") (part "RC0805FR-0710KL"))
    )
    (comp (ref "R5")
      (value "22R")
      (footprint "R0805")
      (description "SMD Chip Resistor, 22 Ohm, ± 1%, 125 mW, 0805 [2012 Metric], Thick Film, General Purpose")
      (fields
        (field (name "MANUFACTURER") "Yageo")
        (field (name "MANUFACTURER PART NUMBER") "RC0805FR-0722RL")
      )
      (libsource (lib "Librerias esquema") (part "RC0805FR-0722RL"))
    )
    (comp (ref "R6")
      (value "22R")
      (footprint "R0805")
      (description "SMD Chip Resistor, 22 Ohm, ± 1%, 125 mW, 0805 [2012 Metric], Thick Film, General Purpose")
      (fields
        (field (name "MANUFACTURER") "Yageo")
        (field (name "MANUFACTURER PART NUMBER") "RC0805FR-0722RL")
      )
      (libsource (lib "Librerias esquema") (part "RC0805FR-0722RL"))
    )
    (comp (ref "R7")
      (value "22R")
      (footprint "R0805")
      (description "SMD Chip Resistor, 22 Ohm, ± 1%, 125 mW, 0805 [2012 Metric], Thick Film, General Purpose")
      (fields
        (field (name "MANUFACTURER") "Yageo")
        (field (name "MANUFACTURER PART NUMBER") "RC0805FR-0722RL")
      )
      (libsource (lib "Librerias esquema") (part "RC0805FR-0722RL"))
    )
    (comp (ref "R8")
      (value "0R")
      (footprint "R0805")
      (description "Zero Ohm Resistor, Jumper, 0805 [2012 Metric], Thick Film, 125 mW, 2 A, Surface Mount")
      (fields
        (field (name "MANUFACTURER") "Bourns")
        (field (name "MANUFACTURER PART NUMBER") "CR0805AJ/-000EAS")
      )
      (libsource (lib "Librerias esquema") (part "CR0805AJ/-000EAS"))
    )
    (comp (ref "R9")
      (value "1M")
      (footprint "R0805")
      (description "SMD Chip Resistor, 1 Megaohms, ± 1%, 125 mW, 0805 [2012 Metric], Thick Film, General Purpose")
      (fields
        (field (name "MANUFACTURER") "Yageo")
        (field (name "MANUFACTURER PART NUMBER") "RC0805FR-071ML")
      )
      (libsource (lib "Librerias esquema") (part "RC0805FR-071ML"))
    )
    (comp (ref "R10")
      (value "1k")
      (footprint "R0805")
      (description "SMD Chip Resistor, 1 kOhm, ± 1%, 125 mW, 0805 [2012 Metric], Thick Film, General Purpose")
      (fields
        (field (name "MANUFACTURER") "Yageo")
        (field (name "MANUFACTURER PART NUMBER") "RC0805FR-071KL")
      )
      (libsource (lib "Librerias esquema") (part "RC0805FR-071KL"))
    )
    (comp (ref "R11")
      (value "1k")
      (footprint "R0805")
      (description "SMD Chip Resistor, 1 kOhm, ± 1%, 125 mW, 0805 [2012 Metric], Thick Film, General Purpose")
      (fields
        (field (name "MANUFACTURER") "Yageo")
        (field (name "MANUFACTURER PART NUMBER") "RC0805FR-071KL")
      )
      (libsource (lib "Librerias esquema") (part "RC0805FR-071KL"))
    )
    (comp (ref "R12")
      (value "1k")
      (footprint "R0805")
      (description "SMD Chip Resistor, 1 kOhm, ± 1%, 125 mW, 0805 [2012 Metric], Thick Film, General Purpose")
      (fields
        (field (name "MANUFACTURER") "Yageo")
        (field (name "MANUFACTURER PART NUMBER") "RC0805FR-071KL")
      )
      (libsource (lib "Librerias esquema") (part "RC0805FR-071KL"))
    )
    (comp (ref "R13")
      (value "22R")
      (footprint "R0805")
      (description "SMD Chip Resistor, 22 Ohm, ± 1%, 125 mW, 0805 [2012 Metric], Thick Film, General Purpose")
      (fields
        (field (name "MANUFACTURER") "Yageo")
        (field (name "MANUFACTURER PART NUMBER") "RC0805FR-0722RL")
      )
      (libsource (lib "Librerias esquema") (part "RC0805FR-0722RL"))
    )
    (comp (ref "R14")
      (value "10k")
      (footprint "0805")
      (description "SMD Chip Resistor, 10 kOhm, ± 1%, 125 mW, 0805 [2012 Metric], Thick Film, General Purpose")
      (fields
        (field (name "MANUFACTURER") "Yageo")
        (field (name "MANUFACTURER PART NUMBER") "RC0805FR-0710KL")
      )
      (libsource (lib "Librerias esquema") (part "RC0805FR-0710KL"))
    )
    (comp (ref "R15")
      (value "560R")
      (footprint "R0805")
      (description "Res General Purpose Thick Film 0805 560 Ohm 1% 1/8W ±100ppm/°C Molded Paper T/R")
      (fields
        (field (name "MANUFACTURER") "Yageo")
        (field (name "MANUFACTURER PART NUMBER") "RC0805FR-07560RL")
      )
      (libsource (lib "Librerias esquema") (part "RC0805FR-07560RL"))
    )
    (comp (ref "R16")
      (value "1M")
      (footprint "R0805")
      (description "SMD Chip Resistor, 1 Megaohms, ± 1%, 125 mW, 0805 [2012 Metric], Thick Film, General Purpose")
      (fields
        (field (name "MANUFACTURER") "Yageo")
        (field (name "MANUFACTURER PART NUMBER") "RC0805FR-071ML")
      )
      (libsource (lib "Librerias esquema") (part "RC0805FR-071ML"))
    )
    (comp (ref "R17")
      (value "560R")
      (footprint "R0805")
      (description "Res General Purpose Thick Film 0805 560 Ohm 1% 1/8W ±100ppm/°C Molded Paper T/R")
      (fields
        (field (name "MANUFACTURER") "Yageo")
        (field (name "MANUFACTURER PART NUMBER") "RC0805FR-07560RL")
      )
      (libsource (lib "Librerias esquema") (part "RC0805FR-07560RL"))
    )
    (comp (ref "R18")
      (value "10k")
      (footprint "0805")
      (description "SMD Chip Resistor, 10 kOhm, ± 1%, 125 mW, 0805 [2012 Metric], Thick Film, General Purpose")
      (fields
        (field (name "MANUFACTURER") "Yageo")
        (field (name "MANUFACTURER PART NUMBER") "RC0805FR-0710KL")
      )
      (libsource (lib "Librerias esquema") (part "RC0805FR-0710KL"))
    )
    (comp (ref "R19")
      (value "10k")
      (footprint "0805")
      (description "SMD Chip Resistor, 10 kOhm, ± 1%, 125 mW, 0805 [2012 Metric], Thick Film, General Purpose")
      (fields
        (field (name "MANUFACTURER") "Yageo")
        (field (name "MANUFACTURER PART NUMBER") "RC0805FR-0710KL")
      )
      (libsource (lib "Librerias esquema") (part "RC0805FR-0710KL"))
    )
    (comp (ref "R20")
      (value "10k")
      (footprint "0805")
      (description "SMD Chip Resistor, 10 kOhm, ± 1%, 125 mW, 0805 [2012 Metric], Thick Film, General Purpose")
      (fields
        (field (name "MANUFACTURER") "Yageo")
        (field (name "MANUFACTURER PART NUMBER") "RC0805FR-0710KL")
      )
      (libsource (lib "Librerias esquema") (part "RC0805FR-0710KL"))
    )
    (comp (ref "R21")
      (value "10k")
      (footprint "0805")
      (description "SMD Chip Resistor, 10 kOhm, ± 1%, 125 mW, 0805 [2012 Metric], Thick Film, General Purpose")
      (fields
        (field (name "MANUFACTURER") "Yageo")
        (field (name "MANUFACTURER PART NUMBER") "RC0805FR-0710KL")
      )
      (libsource (lib "Librerias esquema") (part "RC0805FR-0710KL"))
    )
    (comp (ref "R22")
      (value "560R")
      (footprint "R0805")
      (description "Res General Purpose Thick Film 0805 560 Ohm 1% 1/8W ±100ppm/°C Molded Paper T/R")
      (fields
        (field (name "MANUFACTURER") "Yageo")
        (field (name "MANUFACTURER PART NUMBER") "RC0805FR-07560RL")
      )
      (libsource (lib "Librerias esquema") (part "RC0805FR-07560RL"))
    )
    (comp (ref "R23")
      (value "22R")
      (footprint "R0805")
      (description "SMD Chip Resistor, 22 Ohm, ± 1%, 125 mW, 0805 [2012 Metric], Thick Film, General Purpose")
      (fields
        (field (name "MANUFACTURER") "Yageo")
        (field (name "MANUFACTURER PART NUMBER") "RC0805FR-0722RL")
      )
      (libsource (lib "Librerias esquema") (part "RC0805FR-0722RL"))
    )
    (comp (ref "R24")
      (value "22R")
      (footprint "R0805")
      (description "SMD Chip Resistor, 22 Ohm, ± 1%, 125 mW, 0805 [2012 Metric], Thick Film, General Purpose")
      (fields
        (field (name "MANUFACTURER") "Yageo")
        (field (name "MANUFACTURER PART NUMBER") "RC0805FR-0722RL")
      )
      (libsource (lib "Librerias esquema") (part "RC0805FR-0722RL"))
    )
    (comp (ref "R25")
      (value "22R")
      (footprint "R0805")
      (description "SMD Chip Resistor, 22 Ohm, ± 1%, 125 mW, 0805 [2012 Metric], Thick Film, General Purpose")
      (fields
        (field (name "MANUFACTURER") "Yageo")
        (field (name "MANUFACTURER PART NUMBER") "RC0805FR-0722RL")
      )
      (libsource (lib "Librerias esquema") (part "RC0805FR-0722RL"))
    )
    (comp (ref "R26")
      (value "0R")
      (footprint "R0805")
      (description "Zero Ohm Resistor, Jumper, 0805 [2012 Metric], Thick Film, 125 mW, 2 A, Surface Mount")
      (fields
        (field (name "MANUFACTURER") "Bourns")
        (field (name "MANUFACTURER PART NUMBER") "CR0805AJ/-000EAS")
      )
      (libsource (lib "Librerias esquema") (part "CR0805AJ/-000EAS"))
    )
    (comp (ref "R27")
      (value "0R")
      (footprint "R0805")
      (description "Zero Ohm Resistor, Jumper, 0805 [2012 Metric], Thick Film, 125 mW, 2 A, Surface Mount")
      (fields
        (field (name "MANUFACTURER") "Bourns")
        (field (name "MANUFACTURER PART NUMBER") "CR0805AJ/-000EAS")
      )
      (libsource (lib "Librerias esquema") (part "CR0805AJ/-000EAS"))
    )
    (comp (ref "R28")
      (value "0R")
      (footprint "R0805")
      (description "Zero Ohm Resistor, Jumper, 0805 [2012 Metric], Thick Film, 125 mW, 2 A, Surface Mount")
      (fields
        (field (name "MANUFACTURER") "Bourns")
        (field (name "MANUFACTURER PART NUMBER") "CR0805AJ/-000EAS")
      )
      (libsource (lib "Librerias esquema") (part "CR0805AJ/-000EAS"))
    )
    (comp (ref "SCKT FOR U1")
      (value "28DIP_SOCKET")
      (footprint "DIP28_7.62mm_Socket")
      (description "Socket DIP 28Cnts DualWipe 0.3InSpc. PhosphorBronze Nickel KinkedTail 4800Series ¦ 3M 4828-3004-CP")
      (fields (field (name "MANUFACTURER") "3M") (field (name "MANUFACTURER PART NUMBER") "4828-3004-CP"))
      (libsource (lib "Librerias esquema") (part "4828-3004-CP"))
    )
    (comp (ref "SW1")
      (value "1825910-6")
      (footprint "SW 2x2")
      (description "Alcoswitch, Switch, Pushbutton, Tactile, SPST, 50mA, Thru Hole, 6mm ¦ TE Connectivity FSM4JH")
      (fields (field (name "MANUFACTURER") "TE Connectivity Alcoswitch"))
      (libsource (lib "Librerias esquema") (part "1825910-6"))
    )
    (comp (ref "SW2")
      (value "1825910-6")
      (footprint "SW 2x2")
      (description "Alcoswitch, Switch, Pushbutton, Tactile, SPST, 50mA, Thru Hole, 6mm ¦ TE Connectivity FSM4JH")
      (fields (field (name "MANUFACTURER") "TE Connectivity Alcoswitch"))
      (libsource (lib "Librerias esquema") (part "1825910-6"))
    )
    (comp (ref "U1")
      (value "ATMEGA328P-PU")
      (footprint "DIP28_U1")
      (description "Microchip - ATMEGA328P-PU - Microcontroller Mcu, 8 Bit, Atmega, 20MHZ, DIP-28")
      (fields (field (name "MANUFACTURER") "Microchip"))
      (libsource (lib "Librerias esquema") (part "ATMEGA328P-PU"))
    )
    (comp (ref "U2")
      (value "ATMEGA16U2-AU")
      (footprint "TQFP32")
      (description "Risc Microcontroller, 8-BIT, Flash, AVR Risc Cpu, 16MHZ, Cmos, PQFP32")
      (fields (field (name "MANUFACTURER") "Microchip"))
      (libsource (lib "Librerias esquema") (part "ATMEGA16U2-AU"))
    )
    (comp (ref "U3")
      (value "TL1963A-33DCQR")
      (footprint "DCQ (RPDSO-G6)")
      (description "LDO Regulator Pos 3.3V 1.5A 6-Pin(5+Tab) SOT-223 T/R")
      (fields (field (name "MANUFACTURER") "Texas Instruments"))
      (libsource (lib "Librerias esquema") (part "TL1963A-33DCQR"))
    )
    (comp (ref "U4")
      (value "SN74AHC1G09DBVR")
      (footprint "DBV-SOT23-5")
      (description "1-ch, 2-input 2-V to 5.5-V high-speed (9 ns) AND gate with open-drain outputs 5-SOT-23 -55 to 125")
      (fields (field (name "MANUFACTURER") "Texas Instruments"))
      (libsource (lib "Librerias esquema") (part "SN74AHC1G09DBVR"))
    )
    (comp (ref "U5")
      (value "SN74AHC1G09DBVR")
      (footprint "DBV-SOT23-5")
      (description "1-ch, 2-input 2-V to 5.5-V high-speed (9 ns) AND gate with open-drain outputs 5-SOT-23 -55 to 125")
      (fields (field (name "MANUFACTURER") "Texas Instruments"))
      (libsource (lib "Librerias esquema") (part "SN74AHC1G09DBVR"))
    )
    (comp (ref "U6")
      (value "SN74AHC1G09DBVR")
      (footprint "DBV-SOT23-5")
      (description "1-ch, 2-input 2-V to 5.5-V high-speed (9 ns) AND gate with open-drain outputs 5-SOT-23 -55 to 125")
      (fields (field (name "MANUFACTURER") "Texas Instruments"))
      (libsource (lib "Librerias esquema") (part "SN74AHC1G09DBVR"))
    )
    (comp (ref "U7")
      (value "SN74AHC1G09DBVR")
      (footprint "DBV-SOT23-5")
      (description "1-ch, 2-input 2-V to 5.5-V high-speed (9 ns) AND gate with open-drain outputs 5-SOT-23 -55 to 125")
      (fields (field (name "MANUFACTURER") "Texas Instruments"))
      (libsource (lib "Librerias esquema") (part "SN74AHC1G09DBVR"))
    )
    (comp (ref "Y1")
      (value "ABM7-16.000MHZ-D2Y-T")
      (footprint "ABM7")
      (description "Crystal 16MHz ±20ppm (Tol) ±30ppm (Stability) 18pF FUND 50Ohm 2-Pin Mini-CSMD T/R")
      (fields (field (name "MANUFACTURER") "Abracon"))
      (libsource (lib "Librerias esquema") (part "ABM7-16.000MHZ-D2Y-T"))
    )
    (comp (ref "Y2")
      (value "ABM7-16.000MHZ-D2Y-T")
      (footprint "ABM7")
      (description "Crystal 16MHz ±20ppm (Tol) ±30ppm (Stability) 18pF FUND 50Ohm 2-Pin Mini-CSMD T/R")
      (fields (field (name "MANUFACTURER") "Abracon"))
      (libsource (lib "Librerias esquema") (part "ABM7-16.000MHZ-D2Y-T"))
    )
    (comp (ref "Z1")
      (value "CG0603MLC-05E")
      (footprint "R0603")
      (description "ESD Suppressor Multilayer Varistor 5V Automotive 2-Pin Case 0603(1608Metric) T/R")
      (fields (field (name "MANUFACTURER") "Bourns") (field (name "VOLTAGE") "5V"))
      (libsource (lib "Librerias esquema") (part "CG0603MLC-05E"))
    )
    (comp (ref "Z2")
      (value "CG0603MLC-05E")
      (footprint "R0603")
      (description "ESD Suppressor Multilayer Varistor 5V Automotive 2-Pin Case 0603(1608Metric) T/R")
      (fields (field (name "MANUFACTURER") "Bourns") (field (name "VOLTAGE") "5V"))
      (libsource (lib "Librerias esquema") (part "CG0603MLC-05E"))
    )
  )
  (nets
    (net (code "1") (name "+3V3") (class "Default")
      (node (ref "C13") (pin "2") (pinfunction "2_2") (pintype "passive"))
      (node (ref "C16") (pin "2") (pinfunction "2_2") (pintype "passive"))
      (node (ref "J1") (pin "4") (pinfunction "4_4") (pintype "passive"))
      (node (ref "JP4") (pin "3") (pinfunction "3_3") (pintype "passive"))
      (node (ref "R28") (pin "2") (pinfunction "2_2") (pintype "passive"))
      (node (ref "U3") (pin "4") (pinfunction "OUT_4") (pintype "passive"))
      (node (ref "U3") (pin "5") (pinfunction "SENSE_5") (pintype "passive"))
    )
    (net (code "2") (name "+5V") (class "Default")
      (node (ref "C12") (pin "2") (pinfunction "2_2") (pintype "passive"))
      (node (ref "C14") (pin "2") (pinfunction "2_2") (pintype "passive"))
      (node (ref "C2") (pin "1") (pinfunction "1_1") (pintype "passive"))
      (node (ref "C6") (pin "2") (pinfunction "2_2") (pintype "passive"))
      (node (ref "J1") (pin "5") (pinfunction "5_5") (pintype "passive"))
      (node (ref "J8") (pin "1") (pinfunction "1_1") (pintype "passive"))
      (node (ref "JP4") (pin "1") (pinfunction "1_1") (pintype "passive"))
      (node (ref "L1") (pin "2") (pinfunction "2_2") (pintype "passive"))
      (node (ref "R27") (pin "1") (pinfunction "1_1") (pintype "passive"))
      (node (ref "U2") (pin "31") (pinfunction "UVCC_31") (pintype "passive"))
      (node (ref "U3") (pin "1") (pinfunction "~{SHDN}_1") (pintype "passive"))
      (node (ref "U3") (pin "2") (pinfunction "IN_2") (pintype "passive"))
    )
    (net (code "3") (name "+5V{slash}3V3") (class "Default")
      (node (ref "C15") (pin "2") (pinfunction "2_2") (pintype "passive"))
      (node (ref "C17") (pin "2") (pinfunction "2_2") (pintype "passive"))
      (node (ref "C26") (pin "2") (pinfunction "2_2") (pintype "passive"))
      (node (ref "C28") (pin "2") (pinfunction "2_2") (pintype "passive"))
      (node (ref "C29") (pin "2") (pinfunction "2_2") (pintype "passive"))
      (node (ref "C30") (pin "2") (pinfunction "2_2") (pintype "passive"))
      (node (ref "C34") (pin "2") (pinfunction "2_2") (pintype "passive"))
      (node (ref "C8") (pin "2") (pinfunction "2_2") (pintype "passive"))
      (node (ref "D5") (pin "1") (pinfunction "Catodo_1") (pintype "passive"))
      (node (ref "D6") (pin "1") (pinfunction "Catodo_1") (pintype "passive"))
      (node (ref "FB1") (pin "1") (pinfunction "1_1") (pintype "passive"))
      (node (ref "FB2") (pin "1") (pinfunction "1_1") (pintype "passive"))
      (node (ref "FB3") (pin "1") (pinfunction "1_1") (pintype "passive"))
      (node (ref "J1") (pin "2") (pinfunction "2_2") (pintype "passive"))
      (node (ref "J5") (pin "2") (pinfunction "2_2") (pintype "passive"))
      (node (ref "J6") (pin "2") (pinfunction "2_2") (pintype "passive"))
      (node (ref "JP4") (pin "2") (pinfunction "2_2") (pintype "passive"))
      (node (ref "R1") (pin "2") (pinfunction "2_2") (pintype "passive"))
      (node (ref "R14") (pin "2") (pinfunction "2_2") (pintype "passive"))
      (node (ref "R15") (pin "2") (pinfunction "2_2") (pintype "passive"))
      (node (ref "R17") (pin "2") (pinfunction "2_2") (pintype "passive"))
      (node (ref "R18") (pin "2") (pinfunction "2_2") (pintype "passive"))
      (node (ref "R19") (pin "2") (pinfunction "2_2") (pintype "passive"))
      (node (ref "R2") (pin "2") (pinfunction "2_2") (pintype "passive"))
      (node (ref "R20") (pin "2") (pinfunction "2_2") (pintype "passive"))
      (node (ref "R21") (pin "2") (pinfunction "2_2") (pintype "passive"))
      (node (ref "R27") (pin "2") (pinfunction "2_2") (pintype "passive"))
      (node (ref "R28") (pin "1") (pinfunction "1_1") (pintype "passive"))
      (node (ref "R3") (pin "2") (pinfunction "2_2") (pintype "passive"))
      (node (ref "R4") (pin "2") (pinfunction "2_2") (pintype "passive"))
      (node (ref "U4") (pin "5") (pintype "passive"))
      (node (ref "U5") (pin "5") (pintype "passive"))
      (node (ref "U6") (pin "5") (pintype "passive"))
      (node (ref "U7") (pin "5") (pintype "passive"))
    )
    (net (code "4") (name "+AREF") (class "Default")
      (node (ref "C21") (pin "2") (pinfunction "2_2") (pintype "passive"))
      (node (ref "C24") (pin "2") (pinfunction "2_2") (pintype "passive"))
      (node (ref "J4") (pin "8") (pinfunction "8_8") (pintype "passive"))
      (node (ref "U1") (pin "21") (pinfunction "AREF_21") (pintype "passive"))
    )
    (net (code "5") (name "/+3V3_16U2_UCAP") (class "Default")
      (node (ref "C7") (pin "2") (pinfunction "2_2") (pintype "passive"))
      (node (ref "R26") (pin "1") (pinfunction "1_1") (pintype "passive"))
      (node (ref "U2") (pin "27") (pinfunction "UCAP_27") (pintype "passive"))
    )
    (net (code "6") (name "/+5V_USB") (class "Default")
      (node (ref "C1") (pin "1") (pinfunction "1_1") (pintype "passive"))
      (node (ref "J7") (pin "1") (pinfunction "1_1") (pintype "passive"))
      (node (ref "L1") (pin "1") (pinfunction "1_1") (pintype "passive"))
    )
    (net (code "7") (name "/+5V{slash}3V3_16U2") (class "Default")
      (node (ref "C3") (pin "2") (pinfunction "2_2") (pintype "passive"))
      (node (ref "C4") (pin "2") (pinfunction "2_2") (pintype "passive"))
      (node (ref "C5") (pin "2") (pinfunction "2_2") (pintype "passive"))
      (node (ref "FB1") (pin "2") (pinfunction "2_2") (pintype "passive"))
      (node (ref "R26") (pin "2") (pinfunction "2_2") (pintype "passive"))
      (node (ref "U2") (pin "32") (pinfunction "AVCC_32") (pintype "passive"))
      (node (ref "U2") (pin "4") (pinfunction "VCC_4") (pintype "passive"))
    )
    (net (code "8") (name "/+5V{slash}3V3_328P_AVCC") (class "Default")
      (node (ref "C22") (pin "2") (pinfunction "2_2") (pintype "passive"))
      (node (ref "C23") (pin "2") (pinfunction "2_2") (pintype "passive"))
      (node (ref "FB3") (pin "2") (pinfunction "2_2") (pintype "passive"))
      (node (ref "U1") (pin "20") (pinfunction "AVCC_20") (pintype "passive"))
    )
    (net (code "9") (name "/+5V{slash}3V3_328P_VCC") (class "Default")
      (node (ref "C19") (pin "2") (pinfunction "2_2") (pintype "passive"))
      (node (ref "C20") (pin "2") (pinfunction "2_2") (pintype "passive"))
      (node (ref "FB2") (pin "2") (pinfunction "2_2") (pintype "passive"))
      (node (ref "U1") (pin "7") (pinfunction "VCC_7") (pintype "passive"))
    )
    (net (code "10") (name "/16U2PROG_328P_RESETn") (class "Default")
      (node (ref "JP1") (pin "2") (pinfunction "2_2") (pintype "passive"))
      (node (ref "R1") (pin "1") (pinfunction "1_1") (pintype "passive"))
      (node (ref "U2") (pin "13") (pinfunction "/_HWB_/_AIN6_/_T0_/_INT7)_PD7_13") (pintype "passive"))
    )
    (net (code "11") (name "/16U2_16MHz_XTAL1") (class "Default")
      (node (ref "C10") (pin "2") (pinfunction "2_2") (pintype "passive"))
      (node (ref "R9") (pin "1") (pinfunction "1_1") (pintype "passive"))
      (node (ref "U2") (pin "1") (pinfunction "XTAL1_1") (pintype "passive"))
      (node (ref "Y2") (pin "1") (pinfunction "1_1") (pintype "passive"))
    )
    (net (code "12") (name "/16U2_16MHz_XTAL2") (class "Default")
      (node (ref "C9") (pin "2") (pinfunction "2_2") (pintype "passive"))
      (node (ref "R9") (pin "2") (pinfunction "2_2") (pintype "passive"))
      (node (ref "U2") (pin "2") (pinfunction "(PC0)_XTAL2_2") (pintype "passive"))
      (node (ref "Y2") (pin "2") (pinfunction "2_2") (pintype "passive"))
    )
    (net (code "13") (name "/16U2_BUF_RESETn") (class "Default")
      (node (ref "C31") (pin "2") (pinfunction "2_2") (pintype "passive"))
      (node (ref "R23") (pin "2") (pinfunction "2_2") (pintype "passive"))
      (node (ref "U5") (pin "1") (pinfunction "1_1") (pintype "passive"))
      (node (ref "U5") (pin "2") (pinfunction "2_2") (pintype "passive"))
    )
    (net (code "14") (name "/16U2_HDR_RESETn") (class "Default")
      (node (ref "J6") (pin "5") (pinfunction "5_5") (pintype "passive"))
      (node (ref "JP3") (pin "3") (pinfunction "3_3") (pintype "passive"))
    )
    (net (code "15") (name "/16U2_MISO") (class "Default")
      (node (ref "J6") (pin "1") (pinfunction "1_1") (pintype "passive"))
      (node (ref "U2") (pin "17") (pinfunction "PB3_(PDO_/_MISO_/_PCINT3)_17") (pintype "passive"))
    )
    (net (code "16") (name "/16U2_MOSI") (class "Default")
      (node (ref "J6") (pin "4") (pinfunction "4_4") (pintype "passive"))
      (node (ref "U2") (pin "16") (pinfunction "(PDI_/_MOSI_/_PCINT2)_PB2_16") (pintype "passive"))
    )
    (net (code "17") (name "/16U2_PB4") (class "Default")
      (node (ref "JP2") (pin "1") (pinfunction "1_1") (pintype "passive"))
      (node (ref "JP3") (pin "2") (pinfunction "2_2") (pintype "passive"))
      (node (ref "U2") (pin "18") (pinfunction "PB4_(T1_/_PCINT4)_18") (pintype "passive"))
    )
    (net (code "18") (name "/16U2_PB5") (class "Default")
      (node (ref "JP2") (pin "3") (pinfunction "3_3") (pintype "passive"))
      (node (ref "U2") (pin "19") (pinfunction "PB5_(PCINT5)_19") (pintype "passive"))
    )
    (net (code "19") (name "/16U2_PB6") (class "Default")
      (node (ref "JP2") (pin "2") (pinfunction "2_2") (pintype "passive"))
      (node (ref "U2") (pin "20") (pinfunction "PB6_(PCINT6)_20") (pintype "passive"))
    )
    (net (code "20") (name "/16U2_PB7") (class "Default")
      (node (ref "JP2") (pin "4") (pinfunction "4_4") (pintype "passive"))
      (node (ref "U2") (pin "21") (pinfunction "PB7_(PCINT7_/_OC.0A_/_OC.1C)_21") (pintype "passive"))
    )
    (net (code "21") (name "/16U2_RESETn") (class "Default")
      (node (ref "JP3") (pin "4") (pinfunction "4_4") (pintype "passive"))
      (node (ref "R4") (pin "1") (pinfunction "1_1") (pintype "passive"))
      (node (ref "U2") (pin "24") (pinfunction "~{Reset}_(PC1_/_dW)_24") (pintype "passive"))
      (node (ref "U5") (pin "4") (pintype "passive"))
    )
    (net (code "22") (name "/16U2_RXD") (class "Default")
      (node (ref "R11") (pin "1") (pinfunction "1_1") (pintype "passive"))
      (node (ref "U2") (pin "8") (pinfunction "(RXD1_/_AIN1_/_INT2)_PD2_8") (pintype "passive"))
    )
    (net (code "23") (name "/16U2_RX_LED") (class "Default")
      (node (ref "D4") (pin "1") (pinfunction "Catodo_1") (pintype "passive"))
      (node (ref "U2") (pin "10") (pinfunction "(INT5/_AIN3)_PD4_10") (pintype "passive"))
    )
    (net (code "24") (name "/16U2_SCLK") (class "Default")
      (node (ref "J6") (pin "3") (pinfunction "3_3") (pintype "passive"))
      (node (ref "R5") (pin "2") (pinfunction "2_2") (pintype "passive"))
    )
    (net (code "25") (name "/16U2_SCLK_R") (class "Default")
      (node (ref "R5") (pin "1") (pinfunction "1_1") (pintype "passive"))
      (node (ref "U2") (pin "15") (pinfunction "(SCLK_/_PCINT1)_PB1_15") (pintype "passive"))
    )
    (net (code "26") (name "/16U2_TXD") (class "Default")
      (node (ref "R10") (pin "1") (pinfunction "1_1") (pintype "passive"))
      (node (ref "U2") (pin "9") (pinfunction "(TXD1_/_INT3)_PD3_9") (pintype "passive"))
    )
    (net (code "27") (name "/16U2_TX_LED") (class "Default")
      (node (ref "D3") (pin "1") (pinfunction "Catodo_1") (pintype "passive"))
      (node (ref "U2") (pin "11") (pinfunction "(XCK_AIN4_/_PCINT12)_PD5_11") (pintype "passive"))
    )
    (net (code "28") (name "/328P_16MHz_XTAL1") (class "Default")
      (node (ref "C27") (pin "2") (pinfunction "2_2") (pintype "passive"))
      (node (ref "R16") (pin "1") (pinfunction "1_1") (pintype "passive"))
      (node (ref "U1") (pin "9") (pinfunction "(PCINT6/XTAL1/TOSC1)_PB6_9") (pintype "passive"))
      (node (ref "Y1") (pin "1") (pinfunction "1_1") (pintype "passive"))
    )
    (net (code "29") (name "/328P_16MHz_XTAL2") (class "Default")
      (node (ref "C25") (pin "2") (pinfunction "2_2") (pintype "passive"))
      (node (ref "R16") (pin "2") (pinfunction "2_2") (pintype "passive"))
      (node (ref "U1") (pin "10") (pinfunction "(PCINT7/XTAL2/TOSC2)_PB7_10") (pintype "passive"))
      (node (ref "Y1") (pin "2") (pinfunction "2_2") (pintype "passive"))
    )
    (net (code "30") (name "/328P_AUTORESETn") (class "Default")
      (node (ref "C11") (pin "1") (pinfunction "1_1") (pintype "passive"))
      (node (ref "R18") (pin "1") (pinfunction "1_1") (pintype "passive"))
      (node (ref "U6") (pin "1") (pinfunction "1_1") (pintype "passive"))
    )
    (net (code "31") (name "/328P_BUF_RESETn") (class "Default")
      (node (ref "C32") (pin "2") (pinfunction "2_2") (pintype "passive"))
      (node (ref "R24") (pin "2") (pinfunction "2_2") (pintype "passive"))
      (node (ref "U6") (pin "2") (pinfunction "2_2") (pintype "passive"))
    )
    (net (code "32") (name "/328P_RESETn") (class "Default")
      (node (ref "J1") (pin "3") (pinfunction "3_3") (pintype "passive"))
      (node (ref "J5") (pin "5") (pinfunction "5_5") (pintype "passive"))
      (node (ref "JP3") (pin "1") (pinfunction "1_1") (pintype "passive"))
      (node (ref "R14") (pin "1") (pinfunction "1_1") (pintype "passive"))
      (node (ref "U1") (pin "1") (pinfunction "(PCINT14/~{RESET})_PC6_1") (pintype "passive"))
      (node (ref "U6") (pin "4") (pintype "passive"))
    )
    (net (code "33") (name "/AD0") (class "Default")
      (node (ref "J2") (pin "1") (pinfunction "1_1") (pintype "passive"))
      (node (ref "U1") (pin "23") (pinfunction "PC0_(ADC0/PCINT8)_23") (pintype "passive"))
    )
    (net (code "34") (name "/AD1") (class "Default")
      (node (ref "J2") (pin "2") (pinfunction "2_2") (pintype "passive"))
      (node (ref "U1") (pin "24") (pinfunction "PC1_(ADC1/PCINT9)_24") (pintype "passive"))
    )
    (net (code "35") (name "/AD2") (class "Default")
      (node (ref "J2") (pin "3") (pinfunction "3_3") (pintype "passive"))
      (node (ref "U1") (pin "25") (pinfunction "PC2_(ADC2/PCINT10)_25") (pintype "passive"))
    )
    (net (code "36") (name "/AD3") (class "Default")
      (node (ref "J2") (pin "4") (pinfunction "4_4") (pintype "passive"))
      (node (ref "U1") (pin "26") (pinfunction "PC3_(ADC3/PCINT11)_26") (pintype "passive"))
    )
    (net (code "37") (name "/AD4{slash}SDA") (class "Default")
      (node (ref "J2") (pin "5") (pinfunction "5_5") (pintype "passive"))
      (node (ref "J4") (pin "9") (pinfunction "9_9") (pintype "passive"))
      (node (ref "U1") (pin "27") (pinfunction "PC4_(ADC4/SDA/PCINT12)_27") (pintype "passive"))
    )
    (net (code "38") (name "/AD5{slash}SCL") (class "Default")
      (node (ref "J2") (pin "6") (pinfunction "6_6") (pintype "passive"))
      (node (ref "J4") (pin "10") (pinfunction "10_10") (pintype "passive"))
      (node (ref "U1") (pin "28") (pinfunction "PC5_(ADC5/SCL/PCINT13)_28") (pintype "passive"))
    )
    (net (code "39") (name "/BUTTON_RESETn") (class "Default")
      (node (ref "D6") (pin "2") (pinfunction "Anodo_2") (pintype "passive"))
      (node (ref "R20") (pin "1") (pinfunction "1_1") (pintype "passive"))
      (node (ref "R24") (pin "1") (pinfunction "1_1") (pintype "passive"))
      (node (ref "SW1") (pin "1") (pinfunction "1_1") (pintype "passive"))
      (node (ref "SW1") (pin "2") (pinfunction "2_2") (pintype "passive"))
    )
    (net (code "40") (name "/CONN_USB_N") (class "Default")
      (node (ref "J7") (pin "2") (pinfunction "gg_2") (pintype "passive"))
      (node (ref "R6") (pin "1") (pinfunction "1_1") (pintype "passive"))
      (node (ref "Z1") (pin "2") (pinfunction "2_2") (pintype "passive"))
    )
    (net (code "41") (name "/CONN_USB_P") (class "Default")
      (node (ref "J7") (pin "3") (pinfunction "gg_3") (pintype "passive"))
      (node (ref "R7") (pin "1") (pinfunction "1_1") (pintype "passive"))
      (node (ref "Z2") (pin "2") (pinfunction "2_2") (pintype "passive"))
    )
    (net (code "42") (name "/IO0") (class "Default")
      (node (ref "J3") (pin "1") (pinfunction "1_1") (pintype "passive"))
      (node (ref "R10") (pin "2") (pinfunction "2_2") (pintype "passive"))
      (node (ref "U1") (pin "2") (pinfunction "PCINT16/RXD)_PD0_2") (pintype "passive"))
    )
    (net (code "43") (name "/IO1") (class "Default")
      (node (ref "J3") (pin "2") (pinfunction "2_2") (pintype "passive"))
      (node (ref "R11") (pin "2") (pinfunction "2_2") (pintype "passive"))
      (node (ref "U1") (pin "3") (pinfunction "(PCINT17/TXD)_PD1_3") (pintype "passive"))
    )
    (net (code "44") (name "/IO2") (class "Default")
      (node (ref "J3") (pin "3") (pinfunction "3_3") (pintype "passive"))
      (node (ref "U1") (pin "4") (pinfunction "(PCINT18/INT0)_PD2_4") (pintype "passive"))
    )
    (net (code "45") (name "/IO3") (class "Default")
      (node (ref "J3") (pin "4") (pinfunction "4_4") (pintype "passive"))
      (node (ref "U1") (pin "5") (pinfunction "(PCINT19/OC2B/INT1)_PD3_5") (pintype "passive"))
    )
    (net (code "46") (name "/IO4") (class "Default")
      (node (ref "J3") (pin "5") (pinfunction "5_5") (pintype "passive"))
      (node (ref "U1") (pin "6") (pinfunction "(PCINT20/XCK/T0)_PD4_6") (pintype "passive"))
    )
    (net (code "47") (name "/IO5") (class "Default")
      (node (ref "J3") (pin "6") (pinfunction "6_6") (pintype "passive"))
      (node (ref "U1") (pin "11") (pinfunction "(PCINT21/OC0B/T1)_PD5_11") (pintype "passive"))
    )
    (net (code "48") (name "/IO6") (class "Default")
      (node (ref "J3") (pin "7") (pinfunction "7_7") (pintype "passive"))
      (node (ref "U1") (pin "12") (pinfunction "(PCINT22/OC0A/AIN0)_PD6_12") (pintype "passive"))
    )
    (net (code "49") (name "/IO7") (class "Default")
      (node (ref "J3") (pin "8") (pinfunction "8_8") (pintype "passive"))
      (node (ref "U1") (pin "13") (pinfunction "(PCINT23/AIN1)_PD7_13") (pintype "passive"))
    )
    (net (code "50") (name "/IO8") (class "Default")
      (node (ref "J4") (pin "1") (pinfunction "1_1") (pintype "passive"))
      (node (ref "R22") (pin "2") (pinfunction "2_2") (pintype "passive"))
      (node (ref "U1") (pin "14") (pinfunction "(PCINT0/CLKO/ICP1)_PB0_14") (pintype "passive"))
    )
    (net (code "51") (name "/IO9") (class "Default")
      (node (ref "J4") (pin "2") (pinfunction "2_2") (pintype "passive"))
      (node (ref "U1") (pin "15") (pinfunction "PB1_(OC1A/PCINT1)_15") (pintype "passive"))
    )
    (net (code "52") (name "/MISO") (class "Default")
      (node (ref "J4") (pin "5") (pinfunction "5_5") (pintype "passive"))
      (node (ref "J5") (pin "1") (pinfunction "1_1") (pintype "passive"))
      (node (ref "U1") (pin "18") (pinfunction "PB4_(MISO/PCINT4)_18") (pintype "passive"))
    )
    (net (code "53") (name "/MOSI") (class "Default")
      (node (ref "J4") (pin "4") (pinfunction "4_4") (pintype "passive"))
      (node (ref "J5") (pin "4") (pinfunction "4_4") (pintype "passive"))
      (node (ref "U1") (pin "17") (pinfunction "PB3_(MOSI/OC2A/PCINT3)_17") (pintype "passive"))
    )
    (net (code "54") (name "/SCK") (class "Default")
      (node (ref "J4") (pin "6") (pinfunction "6_6") (pintype "passive"))
      (node (ref "J5") (pin "3") (pinfunction "3_3") (pintype "passive"))
      (node (ref "R13") (pin "2") (pinfunction "2_2") (pintype "passive"))
      (node (ref "U4") (pin "1") (pinfunction "1_1") (pintype "passive"))
      (node (ref "U4") (pin "2") (pinfunction "2_2") (pintype "passive"))
    )
    (net (code "55") (name "/SCK_R") (class "Default")
      (node (ref "R13") (pin "1") (pinfunction "1_1") (pintype "passive"))
      (node (ref "U1") (pin "19") (pinfunction "PB5_(SCK/PCINT5)_19") (pintype "passive"))
    )
    (net (code "56") (name "/SS") (class "Default")
      (node (ref "J4") (pin "3") (pinfunction "3_3") (pintype "passive"))
      (node (ref "U1") (pin "16") (pinfunction "PB2_(~{SS}/OC1B/PCINT2)_16") (pintype "passive"))
    )
    (net (code "57") (name "/USB_N") (class "Default")
      (node (ref "R6") (pin "2") (pinfunction "2_2") (pintype "passive"))
      (node (ref "U2") (pin "30") (pinfunction "D-_30") (pintype "passive"))
    )
    (net (code "58") (name "/USB_P") (class "Default")
      (node (ref "R7") (pin "2") (pinfunction "2_2") (pintype "passive"))
      (node (ref "U2") (pin "29") (pinfunction "D+_29") (pintype "passive"))
    )
    (net (code "59") (name "/USER_BUTTON") (class "Default")
      (node (ref "R21") (pin "1") (pinfunction "1_1") (pintype "passive"))
      (node (ref "R25") (pin "1") (pinfunction "1_1") (pintype "passive"))
      (node (ref "SW2") (pin "1") (pinfunction "1_1") (pintype "passive"))
      (node (ref "SW2") (pin "2") (pinfunction "2_2") (pintype "passive"))
    )
    (net (code "60") (name "/USER_BUTTON_BUF") (class "Default")
      (node (ref "C33") (pin "2") (pinfunction "2_2") (pintype "passive"))
      (node (ref "R25") (pin "2") (pinfunction "2_2") (pintype "passive"))
      (node (ref "U7") (pin "1") (pinfunction "1_1") (pintype "passive"))
      (node (ref "U7") (pin "2") (pinfunction "2_2") (pintype "passive"))
    )
    (net (code "61") (name "GND") (class "Default")
      (node (ref "C1") (pin "2") (pinfunction "2_2") (pintype "passive"))
      (node (ref "C10") (pin "1") (pinfunction "1_1") (pintype "passive"))
      (node (ref "C12") (pin "1") (pinfunction "1_1") (pintype "passive"))
      (node (ref "C13") (pin "1") (pinfunction "1_1") (pintype "passive"))
      (node (ref "C14") (pin "1") (pinfunction "1_1") (pintype "passive"))
      (node (ref "C15") (pin "1") (pinfunction "1_1") (pintype "passive"))
      (node (ref "C16") (pin "1") (pinfunction "1_1") (pintype "passive"))
      (node (ref "C17") (pin "1") (pinfunction "1_1") (pintype "passive"))
      (node (ref "C19") (pin "1") (pinfunction "1_1") (pintype "passive"))
      (node (ref "C2") (pin "2") (pinfunction "2_2") (pintype "passive"))
      (node (ref "C20") (pin "1") (pinfunction "1_1") (pintype "passive"))
      (node (ref "C21") (pin "1") (pinfunction "1_1") (pintype "passive"))
      (node (ref "C22") (pin "1") (pinfunction "1_1") (pintype "passive"))
      (node (ref "C23") (pin "1") (pinfunction "1_1") (pintype "passive"))
      (node (ref "C24") (pin "1") (pinfunction "1_1") (pintype "passive"))
      (node (ref "C25") (pin "1") (pinfunction "1_1") (pintype "passive"))
      (node (ref "C26") (pin "1") (pinfunction "1_1") (pintype "passive"))
      (node (ref "C27") (pin "1") (pinfunction "1_1") (pintype "passive"))
      (node (ref "C28") (pin "1") (pinfunction "1_1") (pintype "passive"))
      (node (ref "C29") (pin "1") (pinfunction "1_1") (pintype "passive"))
      (node (ref "C3") (pin "1") (pinfunction "1_1") (pintype "passive"))
      (node (ref "C30") (pin "1") (pinfunction "1_1") (pintype "passive"))
      (node (ref "C31") (pin "1") (pinfunction "1_1") (pintype "passive"))
      (node (ref "C32") (pin "1") (pinfunction "1_1") (pintype "passive"))
      (node (ref "C33") (pin "1") (pinfunction "1_1") (pintype "passive"))
      (node (ref "C34") (pin "1") (pinfunction "1_1") (pintype "passive"))
      (node (ref "C4") (pin "1") (pinfunction "1_1") (pintype "passive"))
      (node (ref "C5") (pin "1") (pinfunction "1_1") (pintype "passive"))
      (node (ref "C6") (pin "1") (pinfunction "1_1") (pintype "passive"))
      (node (ref "C7") (pin "1") (pinfunction "1_1") (pintype "passive"))
      (node (ref "C8") (pin "1") (pinfunction "1_1") (pintype "passive"))
      (node (ref "C9") (pin "1") (pinfunction "1_1") (pintype "passive"))
      (node (ref "D1") (pin "1") (pinfunction "Catodo_1") (pintype "passive"))
      (node (ref "J1") (pin "6") (pinfunction "6_6") (pintype "passive"))
      (node (ref "J1") (pin "7") (pinfunction "7_7") (pintype "passive"))
      (node (ref "J4") (pin "7") (pinfunction "7_7") (pintype "passive"))
      (node (ref "J5") (pin "6") (pinfunction "6_6") (pintype "passive"))
      (node (ref "J6") (pin "6") (pinfunction "6_6") (pintype "passive"))
      (node (ref "J7") (pin "10") (pinfunction "gg_10") (pintype "passive"))
      (node (ref "J7") (pin "11") (pinfunction "gg_11") (pintype "passive"))
      (node (ref "J7") (pin "5") (pinfunction "gg_5") (pintype "passive"))
      (node (ref "J7") (pin "6") (pinfunction "gg_6") (pintype "passive"))
      (node (ref "J7") (pin "7") (pinfunction "gg_7") (pintype "passive"))
      (node (ref "J7") (pin "8") (pinfunction "gg_8") (pintype "passive"))
      (node (ref "J7") (pin "9") (pinfunction "gg_9") (pintype "passive"))
      (node (ref "J9") (pin "1") (pinfunction "1_1") (pintype "passive"))
      (node (ref "MH1") (pin "1") (pinfunction "1_1") (pintype "passive"))
      (node (ref "MH2") (pin "1") (pinfunction "1_1") (pintype "passive"))
      (node (ref "MH3") (pin "1") (pinfunction "1_1") (pintype "passive"))
      (node (ref "R12") (pin "1") (pinfunction "1_1") (pintype "passive"))
      (node (ref "R8") (pin "2") (pinfunction "2_2") (pintype "passive"))
      (node (ref "SW1") (pin "3") (pinfunction "3_3") (pintype "passive"))
      (node (ref "SW1") (pin "4") (pinfunction "4_4") (pintype "passive"))
      (node (ref "SW2") (pin "3") (pinfunction "3_3") (pintype "passive"))
      (node (ref "SW2") (pin "4") (pinfunction "4_4") (pintype "passive"))
      (node (ref "U1") (pin "22") (pinfunction "GND_2_22") (pintype "passive"))
      (node (ref "U1") (pin "8") (pinfunction "GND_1_8") (pintype "passive"))
      (node (ref "U2") (pin "28") (pinfunction "UGND_28") (pintype "passive"))
      (node (ref "U2") (pin "3") (pinfunction "GND_3") (pintype "passive"))
      (node (ref "U3") (pin "3") (pinfunction "GND_3") (pintype "passive"))
      (node (ref "U3") (pin "6") (pinfunction "EPAD_6") (pintype "passive"))
      (node (ref "U4") (pin "3") (pinfunction "3_3") (pintype "passive"))
      (node (ref "U5") (pin "3") (pinfunction "3_3") (pintype "passive"))
      (node (ref "U6") (pin "3") (pinfunction "3_3") (pintype "passive"))
      (node (ref "U7") (pin "3") (pinfunction "3_3") (pintype "passive"))
      (node (ref "Z1") (pin "1") (pinfunction "1_1") (pintype "passive"))
      (node (ref "Z2") (pin "1") (pinfunction "1_1") (pintype "passive"))
    )
    (net (code "62") (name "Net-(C11-Pad2)") (class "Default")
      (node (ref "C11") (pin "2") (pinfunction "2_2") (pintype "passive"))
      (node (ref "JP1") (pin "1") (pinfunction "1_1") (pintype "passive"))
    )
    (net (code "63") (name "Net-(D1-Anodo)") (class "Default")
      (node (ref "D1") (pin "2") (pinfunction "Anodo_2") (pintype "passive"))
      (node (ref "R17") (pin "1") (pinfunction "1_1") (pintype "passive"))
    )
    (net (code "64") (name "Net-(D2-Anodo)") (class "Default")
      (node (ref "D2") (pin "2") (pinfunction "Anodo_2") (pintype "passive"))
      (node (ref "R15") (pin "1") (pinfunction "1_1") (pintype "passive"))
    )
    (net (code "65") (name "Net-(D2-Catodo)") (class "Default")
      (node (ref "D2") (pin "1") (pinfunction "Catodo_1") (pintype "passive"))
      (node (ref "U4") (pin "4") (pintype "passive"))
    )
    (net (code "66") (name "Net-(D3-Anodo)") (class "Default")
      (node (ref "D3") (pin "2") (pinfunction "Anodo_2") (pintype "passive"))
      (node (ref "R2") (pin "1") (pinfunction "1_1") (pintype "passive"))
    )
    (net (code "67") (name "Net-(D4-Anodo)") (class "Default")
      (node (ref "D4") (pin "2") (pinfunction "Anodo_2") (pintype "passive"))
      (node (ref "R3") (pin "1") (pinfunction "1_1") (pintype "passive"))
    )
    (net (code "68") (name "Net-(D5-Anodo)") (class "Default")
      (node (ref "D5") (pin "2") (pinfunction "Anodo_2") (pintype "passive"))
      (node (ref "R19") (pin "1") (pinfunction "1_1") (pintype "passive"))
      (node (ref "R23") (pin "1") (pinfunction "1_1") (pintype "passive"))
    )
    (net (code "69") (name "Net-(J7-gg-Pad4)") (class "Default")
      (node (ref "J7") (pin "4") (pinfunction "gg_4") (pintype "passive"))
      (node (ref "R8") (pin "1") (pinfunction "1_1") (pintype "passive"))
    )
    (net (code "70") (name "Net-(JP1-Pad3)") (class "Default")
      (node (ref "JP1") (pin "3") (pinfunction "3_3") (pintype "passive"))
      (node (ref "R12") (pin "2") (pinfunction "2_2") (pintype "passive"))
    )
    (net (code "71") (name "Net-(R22-Pad1)") (class "Default")
      (node (ref "R22") (pin "1") (pinfunction "1_1") (pintype "passive"))
      (node (ref "U7") (pin "4") (pintype "passive"))
    )
    (net (code "72") (name "unconnected-(J1-Pad1)") (class "Default")
      (node (ref "J1") (pin "1") (pinfunction "1_1") (pintype "passive+no_connect"))
    )
    (net (code "73") (name "unconnected-(J1-Pad8)") (class "Default")
      (node (ref "J1") (pin "8") (pinfunction "8_8") (pintype "passive+no_connect"))
    )
    (net (code "74") (name "unconnected-(MH_NC1-Pad1)") (class "Default")
      (node (ref "MH_NC1") (pin "1") (pinfunction "1_1") (pintype "passive+no_connect"))
    )
    (net (code "75") (name "unconnected-(U2-(AIN0_{slash}_INT1)_PD1-Pad7)") (class "Default")
      (node (ref "U2") (pin "7") (pinfunction "(AIN0_/_INT1)_PD1_7") (pintype "passive+no_connect"))
    )
    (net (code "76") (name "unconnected-(U2-(OC.0B_{slash}_INT0)_PD0-Pad6)") (class "Default")
      (node (ref "U2") (pin "6") (pinfunction "(OC.0B_/_INT0)_PD0_6") (pintype "passive+no_connect"))
    )
    (net (code "77") (name "unconnected-(U2-(PCINT11_{slash}AIN2_)_PC2-Pad5)") (class "Default")
      (node (ref "U2") (pin "5") (pinfunction "(PCINT11_/AIN2_)_PC2_5") (pintype "passive+no_connect"))
    )
    (net (code "78") (name "unconnected-(U2-(~{RTS}_{slash}_AIN5_{slash}_INT6)_PD6-Pad12)") (class "Default")
      (node (ref "U2") (pin "12") (pinfunction "(~{RTS}_/_AIN5_/_INT6)_PD6_12") (pintype "passive+no_connect"))
    )
    (net (code "79") (name "unconnected-(U2-(~{SS}_{slash}_PCINT0)_PB0-Pad14)") (class "Default")
      (node (ref "U2") (pin "14") (pinfunction "(~{SS}_/_PCINT0)_PB0_14") (pintype "passive+no_connect"))
    )
    (net (code "80") (name "unconnected-(U2-PC4_(PCINT10)-Pad26)") (class "Default")
      (node (ref "U2") (pin "26") (pinfunction "PC4_(PCINT10)_26") (pintype "passive+no_connect"))
    )
    (net (code "81") (name "unconnected-(U2-PC5_(_PCINT9{slash}_OC.1B)-Pad25)") (class "Default")
      (node (ref "U2") (pin "25") (pinfunction "PC5_(_PCINT9/_OC.1B)_25") (pintype "passive+no_connect"))
    )
    (net (code "82") (name "unconnected-(U2-PC6_(OC.1A_{slash}_PCINT8)-Pad23)") (class "Default")
      (node (ref "U2") (pin "23") (pinfunction "PC6_(OC.1A_/_PCINT8)_23") (pintype "passive+no_connect"))
    )
    (net (code "83") (name "unconnected-(U2-PC7_(INT4_{slash}_ICP1_{slash}_CLKO)-Pad22)") (class "Default")
      (node (ref "U2") (pin "22") (pinfunction "PC7_(INT4_/_ICP1_/_CLKO)_22") (pintype "passive+no_connect"))
    )
  )
)
